# PLT_Demo_V2_R01.net
KiCad netlist of a schematic drawn in EAGLE
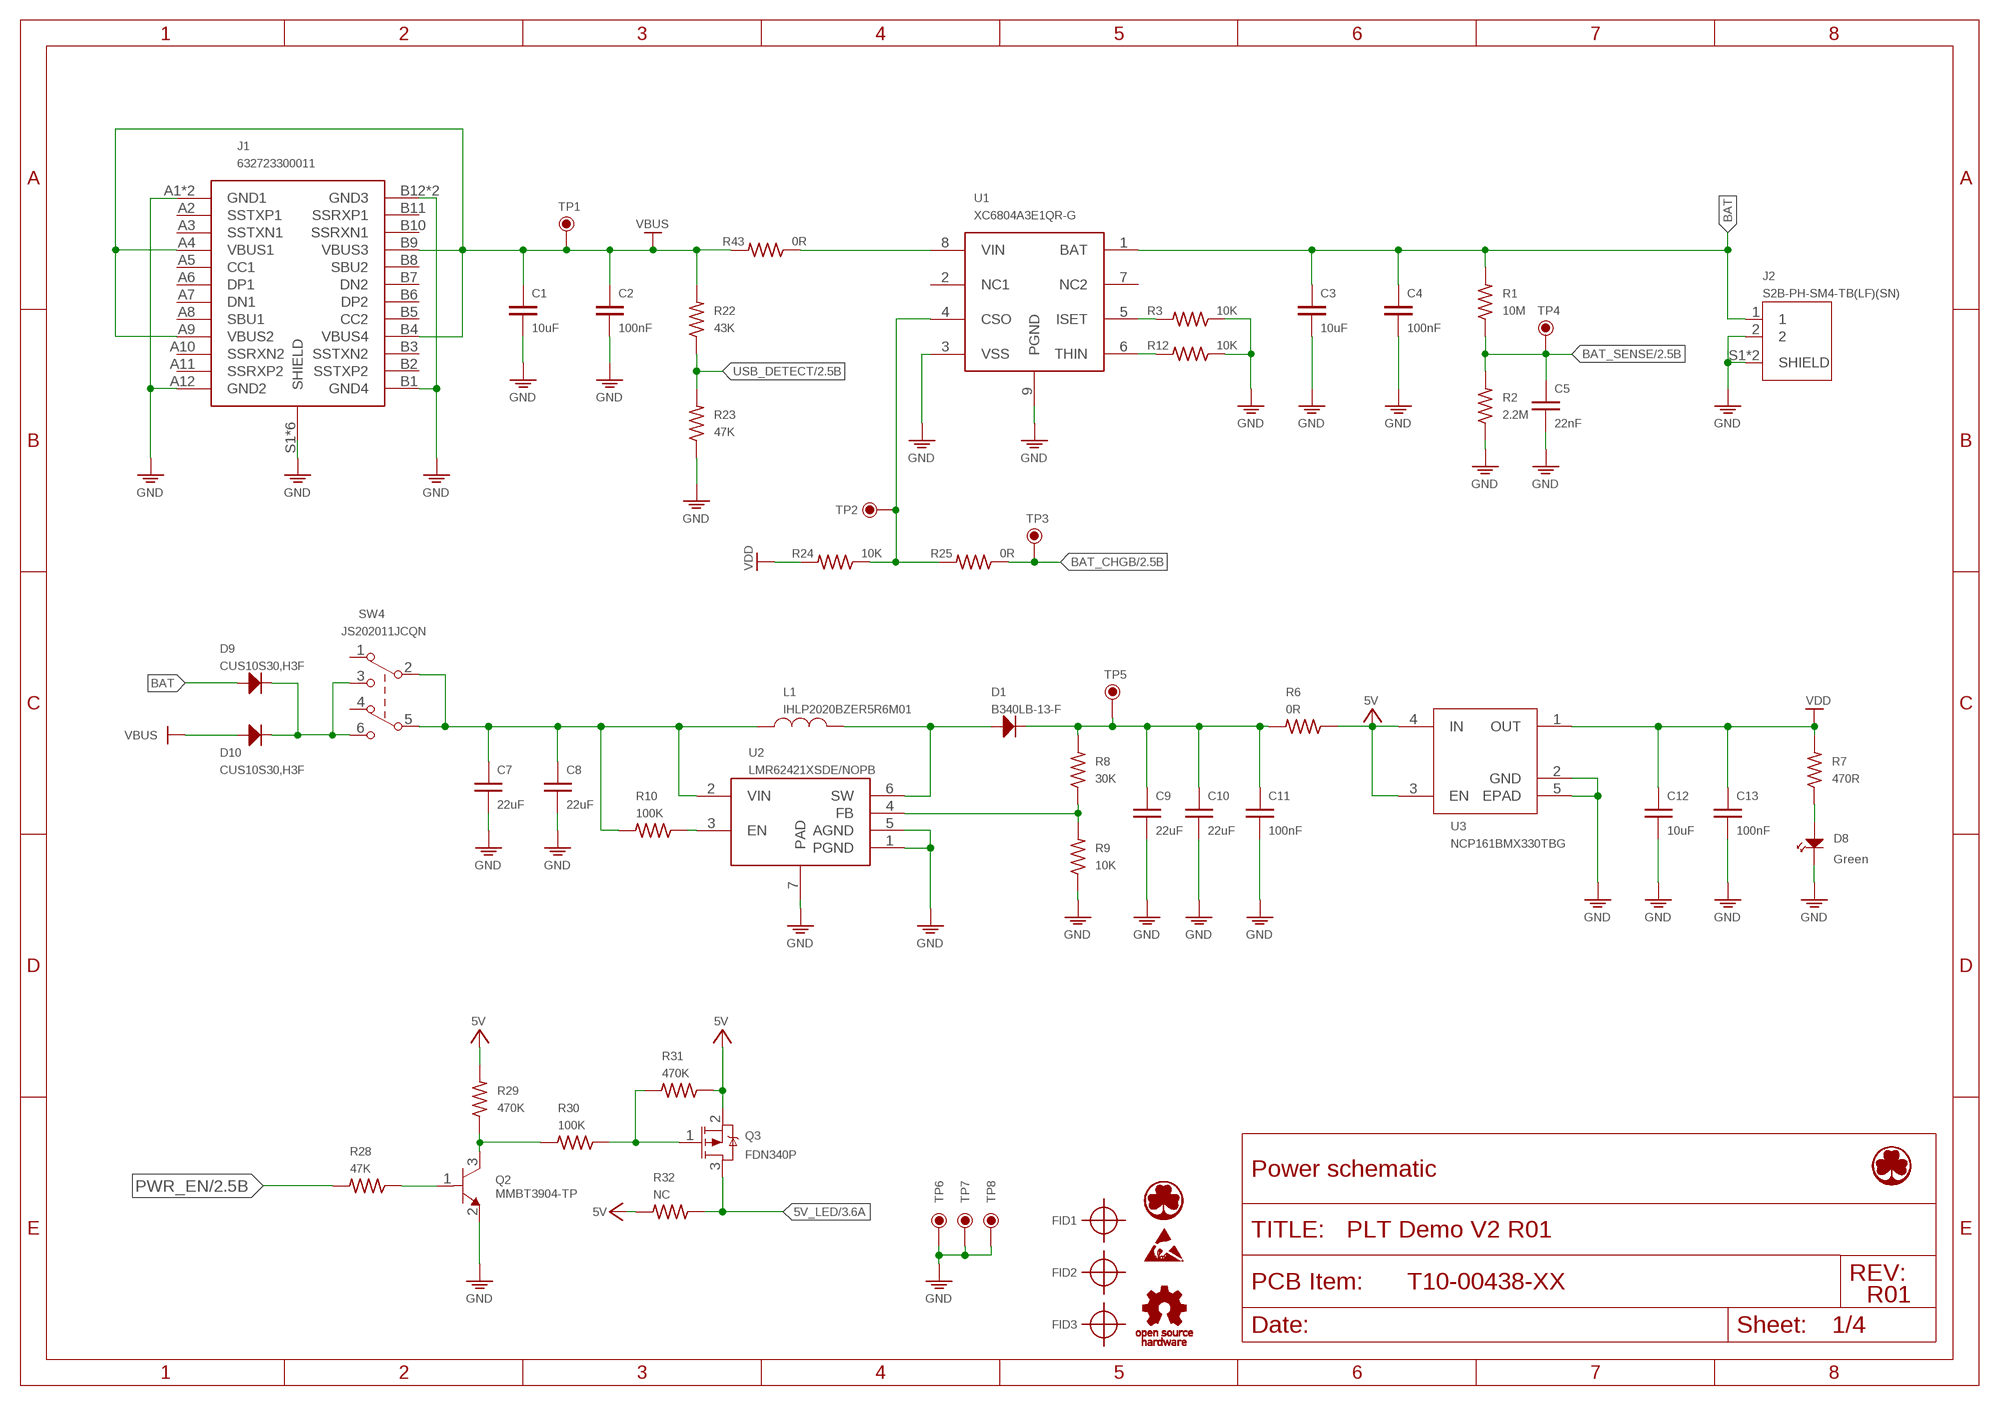
[diagram p0: schematic, sheet 1]
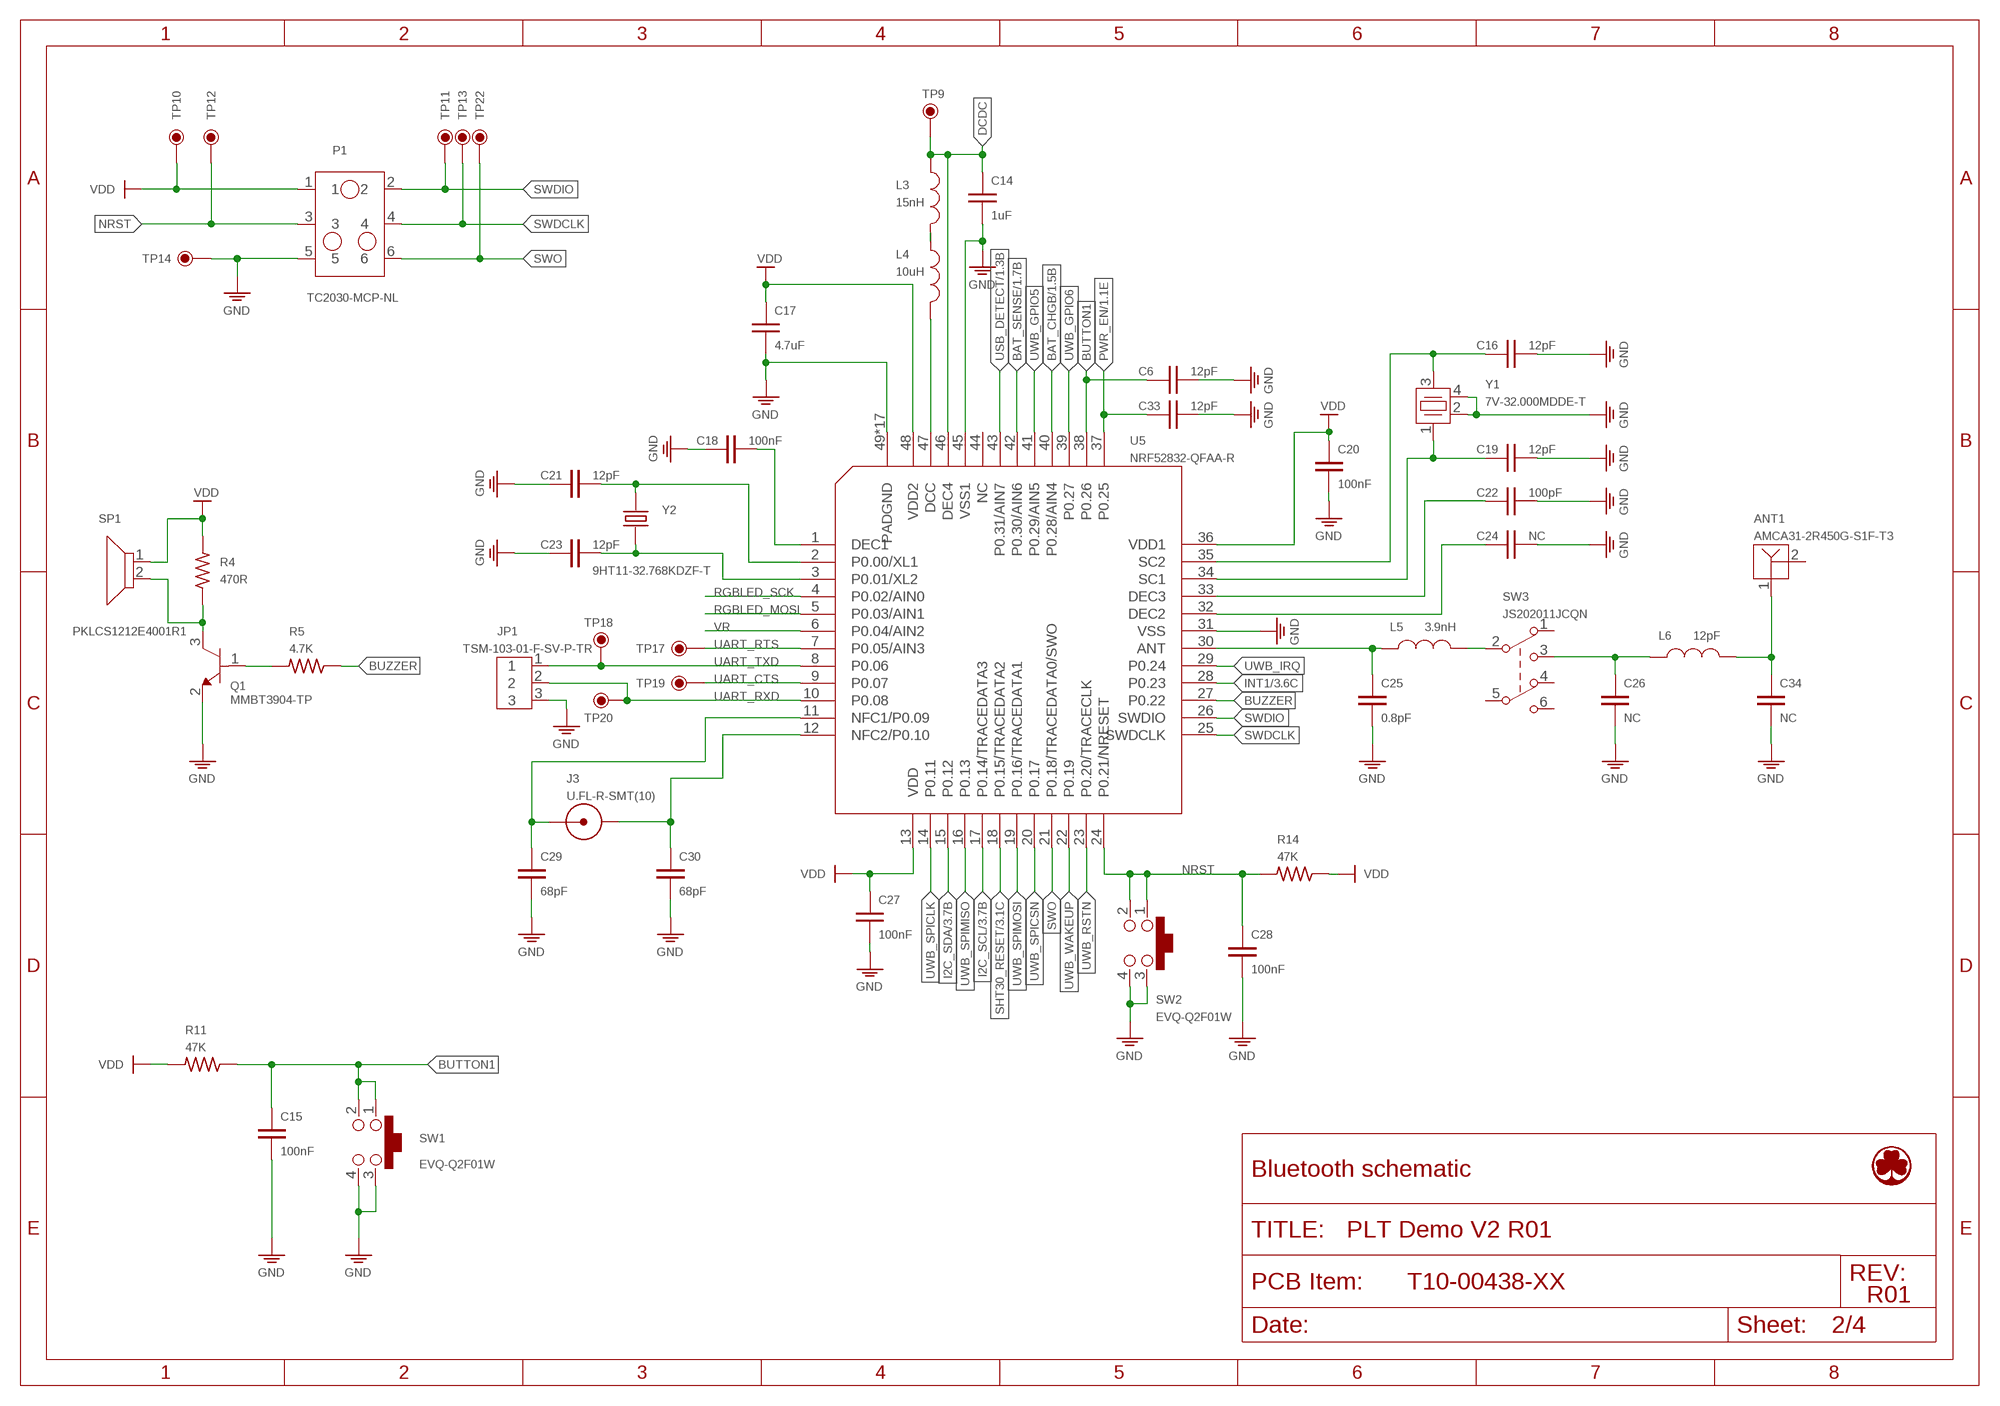
[diagram p1: schematic, sheet 2]
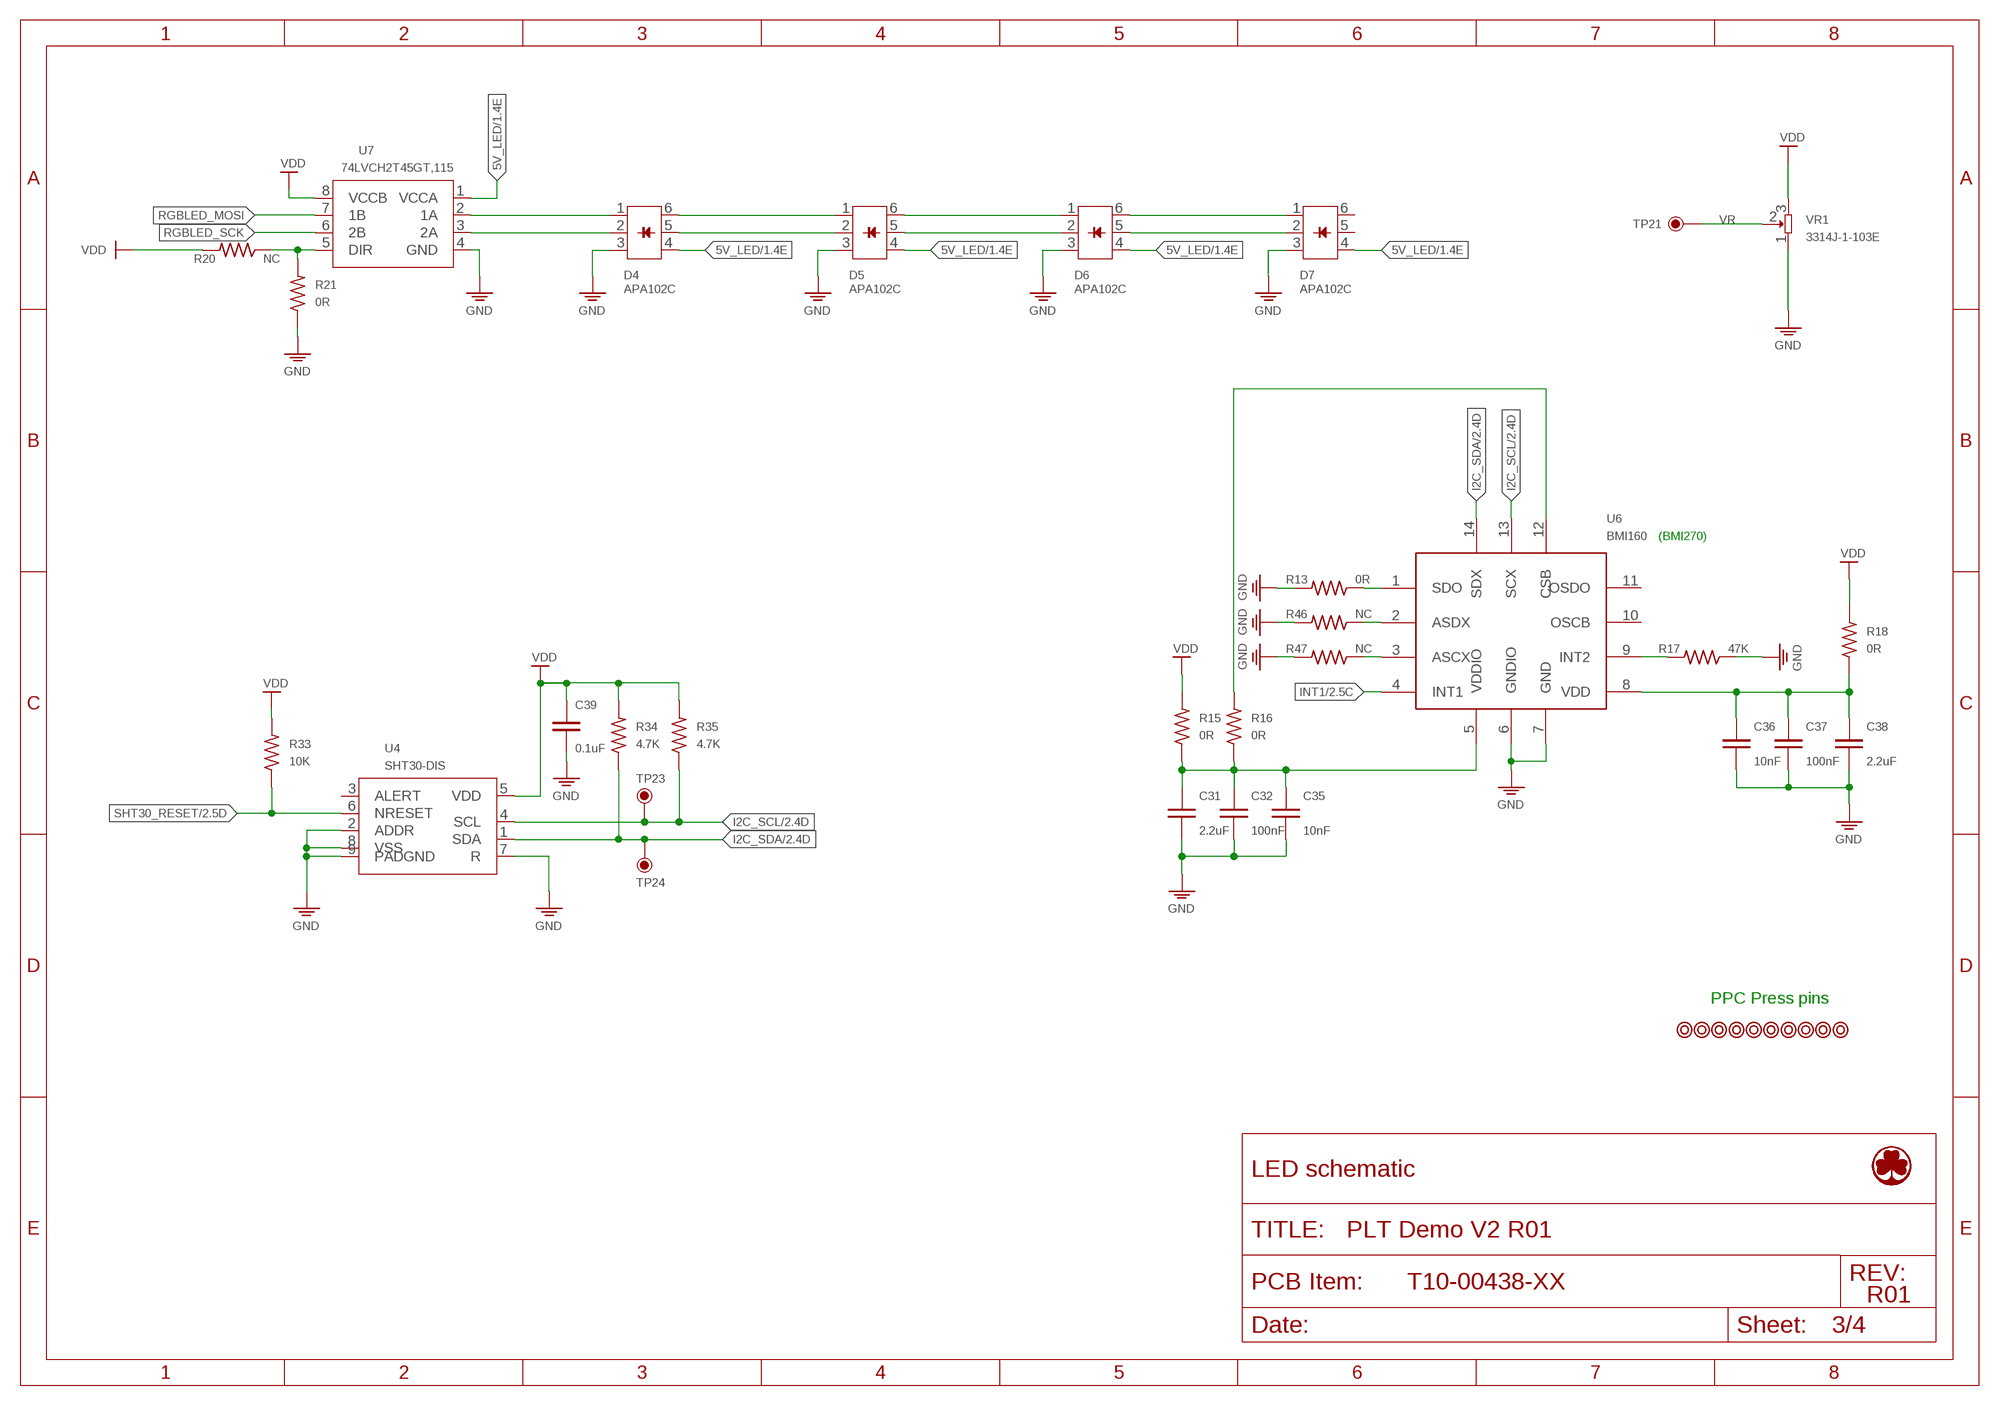
[diagram p2: schematic, sheet 3]
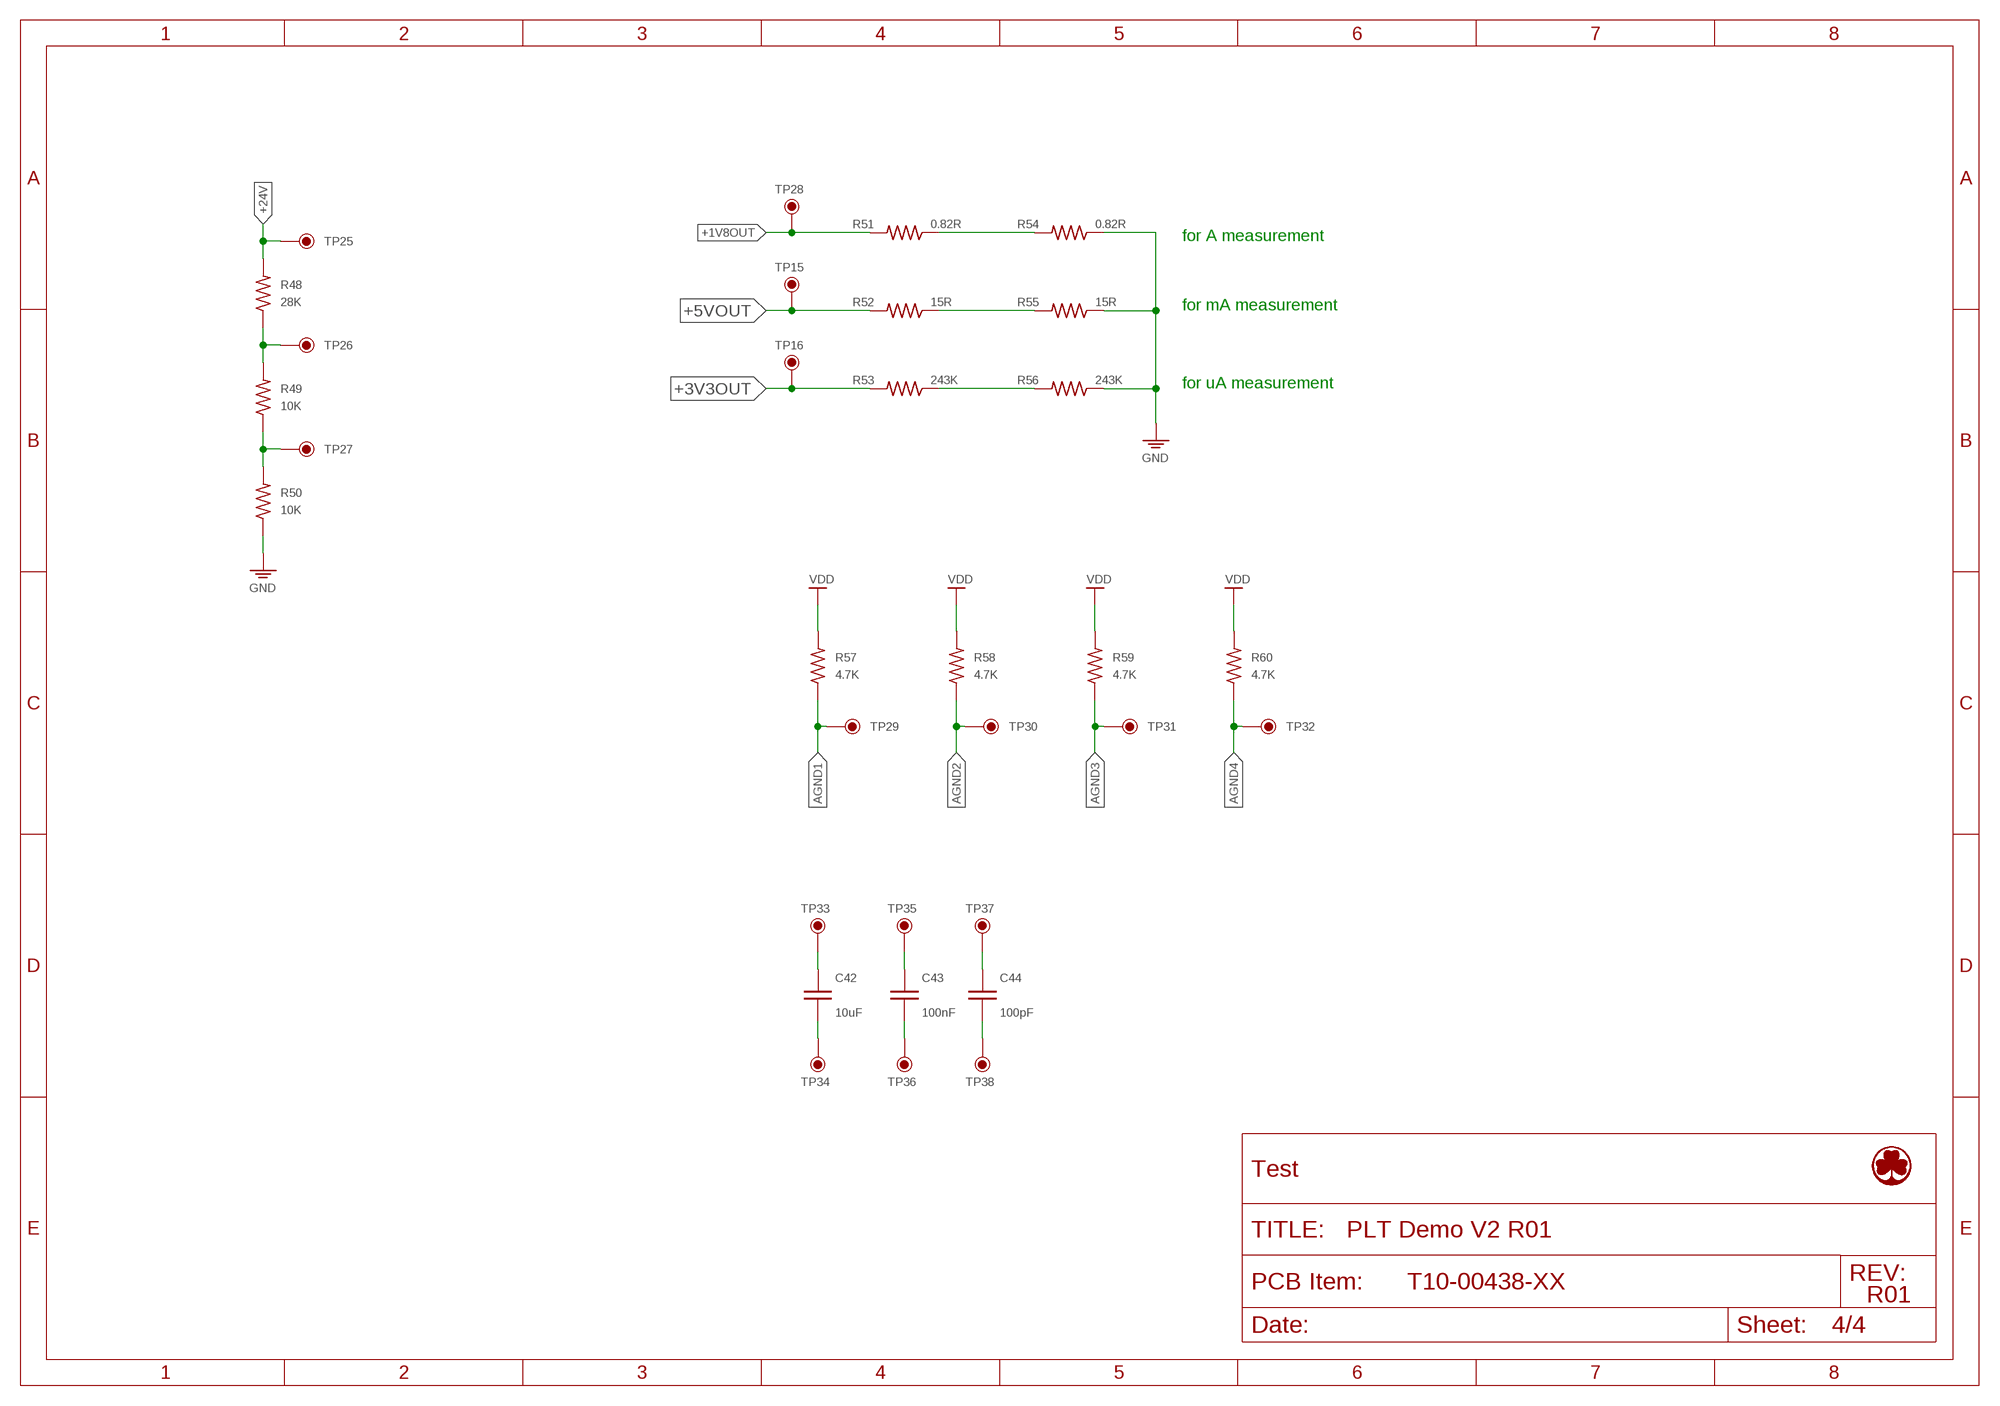
[diagram p3: schematic, sheet 4]

(export (version "E")
  (design (tool "Eeschema 10.0.6"))
  (components
    (comp (ref "ANT1")
      (value "AMCA31-2R450G-S1F-T3")
      (footprint "eagle-import:ANT_3216")
      (libsource (lib "eagle-import") (part "AMCA31-2R450G-S1F-T3"))
    )
    (comp (ref "C6")
      (value "12pF")
      (footprint "eagle-import:C0603")
      (libsource (lib "eagle-import") (part "CAPC0603"))
    )
    (comp (ref "C14")
      (value "1uF")
      (footprint "eagle-import:C0603")
      (libsource (lib "eagle-import") (part "CAPC0603"))
    )
    (comp (ref "C15")
      (value "100nF")
      (footprint "eagle-import:C0603")
      (libsource (lib "eagle-import") (part "CAPC0603"))
    )
    (comp (ref "C16")
      (value "12pF")
      (footprint "eagle-import:C0603")
      (libsource (lib "eagle-import") (part "CAPC0603"))
    )
    (comp (ref "C17")
      (value "4.7uF")
      (footprint "eagle-import:C0603")
      (libsource (lib "eagle-import") (part "CAPC0603"))
    )
    (comp (ref "C18")
      (value "100nF")
      (footprint "eagle-import:C0603")
      (libsource (lib "eagle-import") (part "CAPC0603"))
    )
    (comp (ref "C19")
      (value "12pF")
      (footprint "eagle-import:C0603")
      (libsource (lib "eagle-import") (part "CAPC0603"))
    )
    (comp (ref "C20")
      (value "100nF")
      (footprint "eagle-import:C0603")
      (libsource (lib "eagle-import") (part "CAPC0603"))
    )
    (comp (ref "C21")
      (value "12pF")
      (footprint "eagle-import:C0603")
      (libsource (lib "eagle-import") (part "CAPC0603"))
    )
    (comp (ref "C22")
      (value "100pF")
      (footprint "eagle-import:C0603")
      (libsource (lib "eagle-import") (part "CAPC0603"))
    )
    (comp (ref "C23")
      (value "12pF")
      (footprint "eagle-import:C0603")
      (libsource (lib "eagle-import") (part "CAPC0603"))
    )
    (comp (ref "C24")
      (value "NC")
      (footprint "eagle-import:C0603")
      (libsource (lib "eagle-import") (part "CAPC0603"))
    )
    (comp (ref "C25")
      (value "0.8pF")
      (footprint "eagle-import:C0603")
      (libsource (lib "eagle-import") (part "CAPC0603"))
    )
    (comp (ref "C26")
      (value "NC")
      (footprint "eagle-import:C0603")
      (libsource (lib "eagle-import") (part "CAPC0603"))
    )
    (comp (ref "C27")
      (value "100nF")
      (footprint "eagle-import:C0603")
      (libsource (lib "eagle-import") (part "CAPC0603"))
    )
    (comp (ref "C28")
      (value "100nF")
      (footprint "eagle-import:C0603")
      (libsource (lib "eagle-import") (part "CAPC0603"))
    )
    (comp (ref "C29")
      (value "68pF")
      (footprint "eagle-import:C0603")
      (libsource (lib "eagle-import") (part "CAPC0603"))
    )
    (comp (ref "C30")
      (value "68pF")
      (footprint "eagle-import:C0603")
      (libsource (lib "eagle-import") (part "CAPC0603"))
    )
    (comp (ref "C33")
      (value "12pF")
      (footprint "eagle-import:C0603")
      (libsource (lib "eagle-import") (part "CAPC0603"))
    )
    (comp (ref "C34")
      (value "NC")
      (footprint "eagle-import:C0603")
      (libsource (lib "eagle-import") (part "CAPC0603"))
    )
    (comp (ref "J3")
      (value "U.FL-R-SMT(10)")
      (footprint "eagle-import:U.FL-R-SMT(10)")
      (libsource (lib "eagle-import") (part "U.FL-R-SMT(10)"))
    )
    (comp (ref "JP1")
      (value "TSM-103-01-F-SV-P-TR")
      (footprint "eagle-import:JMP254P1X3V-SMT")
      (libsource (lib "eagle-import") (part "TSM-103-01-F-SV-P-TR"))
    )
    (comp (ref "L3")
      (value "15nH")
      (footprint "eagle-import:IND-0603")
      (libsource (lib "eagle-import") (part "INDUCTOR-2N0603"))
    )
    (comp (ref "L4")
      (value "10uH")
      (footprint "eagle-import:IND-0603")
      (libsource (lib "eagle-import") (part "INDUCTOR-2N0603"))
    )
    (comp (ref "L5")
      (value "3.9nH")
      (footprint "eagle-import:IND-0603")
      (libsource (lib "eagle-import") (part "INDUCTOR-2N0603"))
    )
    (comp (ref "L6")
      (value "12pF")
      (footprint "eagle-import:IND-0603")
      (libsource (lib "eagle-import") (part "INDUCTOR-2N0603"))
    )
    (comp (ref "P1")
      (value "TC2030-MCP-NL")
      (footprint "eagle-import:TC2030-IDC")
      (fields (field (name "MANUFACTURER_PART_NUMBER") "TC2030-MCP-NL-10-ND"))
      (libsource (lib "eagle-import") (part "TC2030-MCP-NL"))
    )
    (comp (ref "Q1")
      (value "MMBT3904-TP")
      (footprint "eagle-import:SOT23")
      (libsource (lib "eagle-import") (part "MMBT3904-TP"))
    )
    (comp (ref "R4")
      (value "470R")
      (footprint "eagle-import:R0603")
      (libsource (lib "eagle-import") (part "RESISTOR_USR0603"))
    )
    (comp (ref "R5")
      (value "4.7K")
      (footprint "eagle-import:R0603")
      (libsource (lib "eagle-import") (part "RESISTOR_USR0603"))
    )
    (comp (ref "R11")
      (value "47K")
      (footprint "eagle-import:R0603")
      (libsource (lib "eagle-import") (part "RESISTOR_USR0603"))
    )
    (comp (ref "R14")
      (value "47K")
      (footprint "eagle-import:R0603")
      (libsource (lib "eagle-import") (part "RESISTOR_USR0603"))
    )
    (comp (ref "SP1")
      (value "PKLCS1212E4001R1")
      (footprint "eagle-import:SPEAKER12X12_SMT")
      (libsource (lib "eagle-import") (part "PKLCS1212E4001R1"))
    )
    (comp (ref "SW1")
      (value "EVQ-Q2F01W")
      (footprint "eagle-import:SWITCH6.5X6_SMD")
      (libsource (lib "eagle-import") (part "SWITCH-4N-SMT"))
    )
    (comp (ref "SW2")
      (value "EVQ-Q2F01W")
      (footprint "eagle-import:SWITCH6.5X6_SMD")
      (libsource (lib "eagle-import") (part "SWITCH-4N-SMT"))
    )
    (comp (ref "SW3")
      (value "JS202011JCQN")
      (footprint "eagle-import:JS202011JCQN")
      (libsource (lib "eagle-import") (part "JS202011JCQN"))
    )
    (comp (ref "TP9")
      (value "TPTP1.0X0.5_DIP")
      (footprint "eagle-import:TP1.0X0.5_DIP")
      (libsource (lib "eagle-import") (part "TPTP1.0X0.5_DIP"))
    )
    (comp (ref "TP10")
      (value "TPTP1.0X0.5_DIP")
      (footprint "eagle-import:TP1.0X0.5_DIP")
      (libsource (lib "eagle-import") (part "TPTP1.0X0.5_DIP"))
    )
    (comp (ref "TP11")
      (value "TPTP1.0X0.5_DIP")
      (footprint "eagle-import:TP1.0X0.5_DIP")
      (libsource (lib "eagle-import") (part "TPTP1.0X0.5_DIP"))
    )
    (comp (ref "TP12")
      (value "TPTP1.0X0.5_DIP")
      (footprint "eagle-import:TP1.0X0.5_DIP")
      (libsource (lib "eagle-import") (part "TPTP1.0X0.5_DIP"))
    )
    (comp (ref "TP13")
      (value "TPTP1.0X0.5_DIP")
      (footprint "eagle-import:TP1.0X0.5_DIP")
      (libsource (lib "eagle-import") (part "TPTP1.0X0.5_DIP"))
    )
    (comp (ref "TP14")
      (value "TPTP1.0X0.5_DIP")
      (footprint "eagle-import:TP1.0X0.5_DIP")
      (libsource (lib "eagle-import") (part "TPTP1.0X0.5_DIP"))
    )
    (comp (ref "TP17")
      (value "TPTP1.0X0.5_DIP")
      (footprint "eagle-import:TP1.0X0.5_DIP")
      (libsource (lib "eagle-import") (part "TPTP1.0X0.5_DIP"))
    )
    (comp (ref "TP18")
      (value "TPTP1.0X0.5_DIP")
      (footprint "eagle-import:TP1.0X0.5_DIP")
      (libsource (lib "eagle-import") (part "TPTP1.0X0.5_DIP"))
    )
    (comp (ref "TP19")
      (value "TPTP1.0X0.5_DIP")
      (footprint "eagle-import:TP1.0X0.5_DIP")
      (libsource (lib "eagle-import") (part "TPTP1.0X0.5_DIP"))
    )
    (comp (ref "TP20")
      (value "TPTP1.0X0.5_DIP")
      (footprint "eagle-import:TP1.0X0.5_DIP")
      (libsource (lib "eagle-import") (part "TPTP1.0X0.5_DIP"))
    )
    (comp (ref "TP22")
      (value "TPTP1.0X0.5_DIP")
      (footprint "eagle-import:TP1.0X0.5_DIP")
      (libsource (lib "eagle-import") (part "TPTP1.0X0.5_DIP"))
    )
    (comp (ref "U5")
      (value "NRF52832-QFAA-R")
      (footprint "eagle-import:QFN040P6X6-48NV")
      (libsource (lib "eagle-import") (part "NRF52832-QFAA-R-48NV"))
    )
    (comp (ref "Y1")
      (value "7V-32.000MDDE-T")
      (footprint "eagle-import:OSC3.2X2.5-4N")
      (libsource (lib "eagle-import") (part "7V-32.000MDDE-T"))
    )
    (comp (ref "Y2")
      (value "9HT11-32.768KDZF-T")
      (footprint "eagle-import:OSC2X1.2-2N")
      (libsource (lib "eagle-import") (part "9HT11-32.768KDZF-T"))
    )
    (comp (ref "C31")
      (value "2.2uF")
      (footprint "eagle-import:C0603")
      (libsource (lib "eagle-import") (part "CAPC0603"))
    )
    (comp (ref "C32")
      (value "100nF")
      (footprint "eagle-import:C0603")
      (libsource (lib "eagle-import") (part "CAPC0603"))
    )
    (comp (ref "C35")
      (value "10nF")
      (footprint "eagle-import:C0603")
      (libsource (lib "eagle-import") (part "CAPC0603"))
    )
    (comp (ref "C36")
      (value "10nF")
      (footprint "eagle-import:C0603")
      (libsource (lib "eagle-import") (part "CAPC0603"))
    )
    (comp (ref "C37")
      (value "100nF")
      (footprint "eagle-import:C0603")
      (libsource (lib "eagle-import") (part "CAPC0603"))
    )
    (comp (ref "C38")
      (value "2.2uF")
      (footprint "eagle-import:C0603")
      (libsource (lib "eagle-import") (part "CAPC0603"))
    )
    (comp (ref "C39")
      (value "0.1uF")
      (footprint "eagle-import:C0603")
      (libsource (lib "eagle-import") (part "CAPC0603"))
    )
    (comp (ref "D4")
      (value "APA102C")
      (footprint "eagle-import:LED5X5-6N")
      (libsource (lib "eagle-import") (part "APA102C"))
    )
    (comp (ref "D5")
      (value "APA102C")
      (footprint "eagle-import:LED5X5-6N")
      (libsource (lib "eagle-import") (part "APA102C"))
    )
    (comp (ref "D6")
      (value "APA102C")
      (footprint "eagle-import:LED5X5-6N")
      (libsource (lib "eagle-import") (part "APA102C"))
    )
    (comp (ref "D7")
      (value "APA102C")
      (footprint "eagle-import:LED5X5-6N")
      (libsource (lib "eagle-import") (part "APA102C"))
    )
    (comp (ref "PIN1")
      (value "PRESS-PINS")
      (footprint "eagle-import:PRESS-PINS")
      (libsource (lib "eagle-import") (part "PRESS-PINS"))
    )
    (comp (ref "PIN2")
      (value "PRESS-PINS")
      (footprint "eagle-import:PRESS-PINS")
      (libsource (lib "eagle-import") (part "PRESS-PINS"))
    )
    (comp (ref "PIN3")
      (value "PRESS-PINS")
      (footprint "eagle-import:PRESS-PINS")
      (libsource (lib "eagle-import") (part "PRESS-PINS"))
    )
    (comp (ref "PIN4")
      (value "PRESS-PINS")
      (footprint "eagle-import:PRESS-PINS")
      (libsource (lib "eagle-import") (part "PRESS-PINS"))
    )
    (comp (ref "PIN5")
      (value "PRESS-PINS")
      (footprint "eagle-import:PRESS-PINS")
      (libsource (lib "eagle-import") (part "PRESS-PINS"))
    )
    (comp (ref "PIN6")
      (value "PRESS-PINS")
      (footprint "eagle-import:PRESS-PINS")
      (libsource (lib "eagle-import") (part "PRESS-PINS"))
    )
    (comp (ref "PIN7")
      (value "PRESS-PINS")
      (footprint "eagle-import:PRESS-PINS")
      (libsource (lib "eagle-import") (part "PRESS-PINS"))
    )
    (comp (ref "PIN8")
      (value "PRESS-PINS")
      (footprint "eagle-import:PRESS-PINS")
      (libsource (lib "eagle-import") (part "PRESS-PINS"))
    )
    (comp (ref "PIN9")
      (value "PRESS-PINS")
      (footprint "eagle-import:PRESS-PINS")
      (libsource (lib "eagle-import") (part "PRESS-PINS"))
    )
    (comp (ref "PIN10")
      (value "PRESS-PINS")
      (footprint "eagle-import:PRESS-PINS")
      (libsource (lib "eagle-import") (part "PRESS-PINS"))
    )
    (comp (ref "R13")
      (value "0R")
      (footprint "eagle-import:R0603")
      (libsource (lib "eagle-import") (part "RESISTOR_USR0603"))
    )
    (comp (ref "R15")
      (value "0R")
      (footprint "eagle-import:R0603")
      (libsource (lib "eagle-import") (part "RESISTOR_USR0603"))
    )
    (comp (ref "R16")
      (value "0R")
      (footprint "eagle-import:R0603")
      (libsource (lib "eagle-import") (part "RESISTOR_USR0603"))
    )
    (comp (ref "R17")
      (value "47K")
      (footprint "eagle-import:R0603")
      (libsource (lib "eagle-import") (part "RESISTOR_USR0603"))
    )
    (comp (ref "R18")
      (value "0R")
      (footprint "eagle-import:R0603")
      (libsource (lib "eagle-import") (part "RESISTOR_USR0603"))
    )
    (comp (ref "R20")
      (value "NC")
      (footprint "eagle-import:R0603")
      (libsource (lib "eagle-import") (part "RESISTOR_USR0603"))
    )
    (comp (ref "R21")
      (value "0R")
      (footprint "eagle-import:R0603")
      (libsource (lib "eagle-import") (part "RESISTOR_USR0603"))
    )
    (comp (ref "R33")
      (value "10K")
      (footprint "eagle-import:R0603")
      (libsource (lib "eagle-import") (part "RESISTOR_USR0603"))
    )
    (comp (ref "R34")
      (value "4.7K")
      (footprint "eagle-import:R0603")
      (libsource (lib "eagle-import") (part "RESISTOR_USR0603"))
    )
    (comp (ref "R35")
      (value "4.7K")
      (footprint "eagle-import:R0603")
      (libsource (lib "eagle-import") (part "RESISTOR_USR0603"))
    )
    (comp (ref "R46")
      (value "NC")
      (footprint "eagle-import:R0603")
      (libsource (lib "eagle-import") (part "RESISTOR_USR0603"))
    )
    (comp (ref "R47")
      (value "NC")
      (footprint "eagle-import:R0603")
      (libsource (lib "eagle-import") (part "RESISTOR_USR0603"))
    )
    (comp (ref "TP21")
      (value "TPTP1.0X0.5_DIP")
      (footprint "eagle-import:TP1.0X0.5_DIP")
      (libsource (lib "eagle-import") (part "TPTP1.0X0.5_DIP"))
    )
    (comp (ref "TP23")
      (value "TPTP1.0X0.5_DIP")
      (footprint "eagle-import:TP1.0X0.5_DIP")
      (libsource (lib "eagle-import") (part "TPTP1.0X0.5_DIP"))
    )
    (comp (ref "TP24")
      (value "TPTP1.0X0.5_DIP")
      (footprint "eagle-import:TP1.0X0.5_DIP")
      (libsource (lib "eagle-import") (part "TPTP1.0X0.5_DIP"))
    )
    (comp (ref "U4")
      (value "SHT30-DIS")
      (footprint "eagle-import:DFN050P2.5X2.5-8N")
      (libsource (lib "eagle-import") (part "SHT30-DISDFN050P2.5X2.5-8N"))
    )
    (comp (ref "U6")
      (value "BMI160")
      (footprint "eagle-import:LGA050P3X2.5-14N")
      (libsource (lib "eagle-import") (part "BMI160"))
    )
    (comp (ref "U7")
      (value "74LVCH2T45GT,115")
      (footprint "eagle-import:XSON8-SOT833-1")
      (libsource (lib "eagle-import") (part "74LVCH2T45GT,115"))
    )
    (comp (ref "VR1")
      (value "3314J-1-103E")
      (footprint "eagle-import:3314J-1-103E")
      (libsource (lib "eagle-import") (part "3314J-1-103E"))
    )
    (comp (ref "C42")
      (value "10uF")
      (footprint "eagle-import:C0805")
      (libsource (lib "eagle-import") (part "CAPC0805"))
    )
    (comp (ref "C43")
      (value "100nF")
      (footprint "eagle-import:C0603")
      (libsource (lib "eagle-import") (part "CAPC0603"))
    )
    (comp (ref "C44")
      (value "100pF")
      (footprint "eagle-import:C0603")
      (libsource (lib "eagle-import") (part "CAPC0603"))
    )
    (comp (ref "R48")
      (value "28K")
      (footprint "eagle-import:R0603")
      (libsource (lib "eagle-import") (part "RESISTOR_USR0603"))
    )
    (comp (ref "R49")
      (value "10K")
      (footprint "eagle-import:R0603")
      (libsource (lib "eagle-import") (part "RESISTOR_USR0603"))
    )
    (comp (ref "R50")
      (value "10K")
      (footprint "eagle-import:R0603")
      (libsource (lib "eagle-import") (part "RESISTOR_USR0603"))
    )
    (comp (ref "R51")
      (value "0.82R")
      (footprint "eagle-import:R1210")
      (libsource (lib "eagle-import") (part "RESISTOR_USR1210"))
    )
    (comp (ref "R52")
      (value "15R")
      (footprint "eagle-import:R0805")
      (libsource (lib "eagle-import") (part "RESISTOR_USR0805"))
    )
    (comp (ref "R53")
      (value "243K")
      (footprint "eagle-import:R0603")
      (libsource (lib "eagle-import") (part "RESISTOR_USR0603"))
    )
    (comp (ref "R54")
      (value "0.82R")
      (footprint "eagle-import:R1210")
      (libsource (lib "eagle-import") (part "RESISTOR_USR1210"))
    )
    (comp (ref "R55")
      (value "15R")
      (footprint "eagle-import:R0805")
      (libsource (lib "eagle-import") (part "RESISTOR_USR0805"))
    )
    (comp (ref "R56")
      (value "243K")
      (footprint "eagle-import:R0603")
      (libsource (lib "eagle-import") (part "RESISTOR_USR0603"))
    )
    (comp (ref "R57")
      (value "4.7K")
      (footprint "eagle-import:R0603")
      (libsource (lib "eagle-import") (part "RESISTOR_USR0603"))
    )
    (comp (ref "R58")
      (value "4.7K")
      (footprint "eagle-import:R0603")
      (libsource (lib "eagle-import") (part "RESISTOR_USR0603"))
    )
    (comp (ref "R59")
      (value "4.7K")
      (footprint "eagle-import:R0603")
      (libsource (lib "eagle-import") (part "RESISTOR_USR0603"))
    )
    (comp (ref "R60")
      (value "4.7K")
      (footprint "eagle-import:R0603")
      (libsource (lib "eagle-import") (part "RESISTOR_USR0603"))
    )
    (comp (ref "TP15")
      (value "TPTP1.0X0.5_DIP")
      (footprint "eagle-import:TP1.0X0.5_DIP")
      (libsource (lib "eagle-import") (part "TPTP1.0X0.5_DIP"))
    )
    (comp (ref "TP16")
      (value "TPTP1.0X0.5_DIP")
      (footprint "eagle-import:TP1.0X0.5_DIP")
      (libsource (lib "eagle-import") (part "TPTP1.0X0.5_DIP"))
    )
    (comp (ref "TP25")
      (value "TPTP1.0X0.5_DIP")
      (footprint "eagle-import:TP1.0X0.5_DIP")
      (libsource (lib "eagle-import") (part "TPTP1.0X0.5_DIP"))
    )
    (comp (ref "TP26")
      (value "TPTP1.0X0.5_DIP")
      (footprint "eagle-import:TP1.0X0.5_DIP")
      (libsource (lib "eagle-import") (part "TPTP1.0X0.5_DIP"))
    )
    (comp (ref "TP27")
      (value "TPTP1.0X0.5_DIP")
      (footprint "eagle-import:TP1.0X0.5_DIP")
      (libsource (lib "eagle-import") (part "TPTP1.0X0.5_DIP"))
    )
    (comp (ref "TP28")
      (value "TPTP1.0X0.5_DIP")
      (footprint "eagle-import:TP1.0X0.5_DIP")
      (libsource (lib "eagle-import") (part "TPTP1.0X0.5_DIP"))
    )
    (comp (ref "TP29")
      (value "TPTP1.0X0.5_DIP")
      (footprint "eagle-import:TP1.0X0.5_DIP")
      (libsource (lib "eagle-import") (part "TPTP1.0X0.5_DIP"))
    )
    (comp (ref "TP30")
      (value "TPTP1.0X0.5_DIP")
      (footprint "eagle-import:TP1.0X0.5_DIP")
      (libsource (lib "eagle-import") (part "TPTP1.0X0.5_DIP"))
    )
    (comp (ref "TP31")
      (value "TPTP1.0X0.5_DIP")
      (footprint "eagle-import:TP1.0X0.5_DIP")
      (libsource (lib "eagle-import") (part "TPTP1.0X0.5_DIP"))
    )
    (comp (ref "TP32")
      (value "TPTP1.0X0.5_DIP")
      (footprint "eagle-import:TP1.0X0.5_DIP")
      (libsource (lib "eagle-import") (part "TPTP1.0X0.5_DIP"))
    )
    (comp (ref "TP33")
      (value "TPTP1.0X0.5_DIP")
      (footprint "eagle-import:TP1.0X0.5_DIP")
      (libsource (lib "eagle-import") (part "TPTP1.0X0.5_DIP"))
    )
    (comp (ref "TP34")
      (value "TPTP1.0X0.5_DIP")
      (footprint "eagle-import:TP1.0X0.5_DIP")
      (libsource (lib "eagle-import") (part "TPTP1.0X0.5_DIP"))
    )
    (comp (ref "TP35")
      (value "TPTP1.0X0.5_DIP")
      (footprint "eagle-import:TP1.0X0.5_DIP")
      (libsource (lib "eagle-import") (part "TPTP1.0X0.5_DIP"))
    )
    (comp (ref "TP36")
      (value "TPTP1.0X0.5_DIP")
      (footprint "eagle-import:TP1.0X0.5_DIP")
      (libsource (lib "eagle-import") (part "TPTP1.0X0.5_DIP"))
    )
    (comp (ref "TP37")
      (value "TPTP1.0X0.5_DIP")
      (footprint "eagle-import:TP1.0X0.5_DIP")
      (libsource (lib "eagle-import") (part "TPTP1.0X0.5_DIP"))
    )
    (comp (ref "TP38")
      (value "TPTP1.0X0.5_DIP")
      (footprint "eagle-import:TP1.0X0.5_DIP")
      (libsource (lib "eagle-import") (part "TPTP1.0X0.5_DIP"))
    )
    (comp (ref "C1")
      (value "10uF")
      (footprint "eagle-import:C0603")
      (libsource (lib "eagle-import") (part "CAPC0603"))
    )
    (comp (ref "C2")
      (value "100nF")
      (footprint "eagle-import:C0603")
      (libsource (lib "eagle-import") (part "CAPC0603"))
    )
    (comp (ref "C3")
      (value "10uF")
      (footprint "eagle-import:C0603")
      (libsource (lib "eagle-import") (part "CAPC0603"))
    )
    (comp (ref "C4")
      (value "100nF")
      (footprint "eagle-import:C0603")
      (libsource (lib "eagle-import") (part "CAPC0603"))
    )
    (comp (ref "C5")
      (value "22nF")
      (footprint "eagle-import:C0603")
      (libsource (lib "eagle-import") (part "CAPC0603"))
    )
    (comp (ref "C7")
      (value "22uF")
      (footprint "eagle-import:C0603")
      (libsource (lib "eagle-import") (part "CAPC0603"))
    )
    (comp (ref "C8")
      (value "22uF")
      (footprint "eagle-import:C0603")
      (libsource (lib "eagle-import") (part "CAPC0603"))
    )
    (comp (ref "C9")
      (value "22uF")
      (footprint "eagle-import:C0603")
      (libsource (lib "eagle-import") (part "CAPC0603"))
    )
    (comp (ref "C10")
      (value "22uF")
      (footprint "eagle-import:C0603")
      (libsource (lib "eagle-import") (part "CAPC0603"))
    )
    (comp (ref "C11")
      (value "100nF")
      (footprint "eagle-import:C0603")
      (libsource (lib "eagle-import") (part "CAPC0603"))
    )
    (comp (ref "C12")
      (value "10uF")
      (footprint "eagle-import:C0603")
      (libsource (lib "eagle-import") (part "CAPC0603"))
    )
    (comp (ref "C13")
      (value "100nF")
      (footprint "eagle-import:C0603")
      (libsource (lib "eagle-import") (part "CAPC0603"))
    )
    (comp (ref "D1")
      (value "B340LB-13-F")
      (footprint "eagle-import:SMB")
      (libsource (lib "eagle-import") (part "B340LB-13-F"))
    )
    (comp (ref "D8")
      (value "Green")
      (footprint "eagle-import:LED0603")
      (libsource (lib "eagle-import") (part "LED-SMTLED0603"))
    )
    (comp (ref "D9")
      (value "CUS10S30,H3F")
      (footprint "eagle-import:SOD-323")
      (libsource (lib "eagle-import") (part "CUS10S30,H3F"))
    )
    (comp (ref "D10")
      (value "CUS10S30,H3F")
      (footprint "eagle-import:SOD-323")
      (libsource (lib "eagle-import") (part "CUS10S30,H3F"))
    )
    (comp (ref "FID1")
      (value "SENSOR_MISC_FIDUCIAL-1MM")
      (footprint "eagle-import:SENSOR_MISC_FIDUCIAL-1MM")
      (libsource (lib "eagle-import") (part "SENSOR_MISC_FIDUCIAL-1MM"))
    )
    (comp (ref "FID2")
      (value "SENSOR_MISC_FIDUCIAL-1MM")
      (footprint "eagle-import:SENSOR_MISC_FIDUCIAL-1MM")
      (libsource (lib "eagle-import") (part "SENSOR_MISC_FIDUCIAL-1MM"))
    )
    (comp (ref "FID3")
      (value "SENSOR_MISC_FIDUCIAL-1MM")
      (footprint "eagle-import:SENSOR_MISC_FIDUCIAL-1MM")
      (libsource (lib "eagle-import") (part "SENSOR_MISC_FIDUCIAL-1MM"))
    )
    (comp (ref "J1")
      (value "632723300011")
      (footprint "eagle-import:632723X00011")
      (libsource (lib "eagle-import") (part "632723X00011"))
    )
    (comp (ref "J2")
      (value "S2B-PH-SM4-TB(LF)(SN)")
      (footprint "eagle-import:S2B-PH-SM4-TB(LF)(SN)")
      (libsource (lib "eagle-import") (part "S2B-PH-SM4-TB(LF)(SN)"))
    )
    (comp (ref "L1")
      (value "IHLP2020BZER5R6M01")
      (footprint "eagle-import:IND-5220_SMD")
      (libsource (lib "eagle-import") (part "IHLP2020BZER5R6M01"))
    )
    (comp (ref "Q2")
      (value "MMBT3904-TP")
      (footprint "eagle-import:SOT23")
      (libsource (lib "eagle-import") (part "MMBT3904-TP"))
    )
    (comp (ref "Q3")
      (value "FDN340P")
      (footprint "eagle-import:SOT23")
      (libsource (lib "eagle-import") (part "FDN340P"))
    )
    (comp (ref "R1")
      (value "10M")
      (footprint "eagle-import:R0603")
      (libsource (lib "eagle-import") (part "RESISTOR_USR0603"))
    )
    (comp (ref "R2")
      (value "2.2M")
      (footprint "eagle-import:R0603")
      (libsource (lib "eagle-import") (part "RESISTOR_USR0603"))
    )
    (comp (ref "R3")
      (value "10K")
      (footprint "eagle-import:R0603")
      (libsource (lib "eagle-import") (part "RESISTOR_USR0603"))
    )
    (comp (ref "R6")
      (value "0R")
      (footprint "eagle-import:R0603")
      (libsource (lib "eagle-import") (part "RESISTOR_USR0603"))
    )
    (comp (ref "R7")
      (value "470R")
      (footprint "eagle-import:R0603")
      (libsource (lib "eagle-import") (part "RESISTOR_USR0603"))
    )
    (comp (ref "R8")
      (value "30K")
      (footprint "eagle-import:R0603")
      (libsource (lib "eagle-import") (part "RESISTOR_USR0603"))
    )
    (comp (ref "R9")
      (value "10K")
      (footprint "eagle-import:R0603")
      (libsource (lib "eagle-import") (part "RESISTOR_USR0603"))
    )
    (comp (ref "R10")
      (value "100K")
      (footprint "eagle-import:R0603")
      (libsource (lib "eagle-import") (part "RESISTOR_USR0603"))
    )
    (comp (ref "R12")
      (value "10K")
      (footprint "eagle-import:R0603")
      (libsource (lib "eagle-import") (part "RESISTOR_USR0603"))
    )
    (comp (ref "R22")
      (value "43K")
      (footprint "eagle-import:R0603")
      (libsource (lib "eagle-import") (part "RESISTOR_USR0603"))
    )
    (comp (ref "R23")
      (value "47K")
      (footprint "eagle-import:R0603")
      (libsource (lib "eagle-import") (part "RESISTOR_USR0603"))
    )
    (comp (ref "R24")
      (value "10K")
      (footprint "eagle-import:R0603")
      (libsource (lib "eagle-import") (part "RESISTOR_USR0603"))
    )
    (comp (ref "R25")
      (value "0R")
      (footprint "eagle-import:R0603")
      (libsource (lib "eagle-import") (part "RESISTOR_USR0603"))
    )
    (comp (ref "R28")
      (value "47K")
      (footprint "eagle-import:R0603")
      (libsource (lib "eagle-import") (part "RESISTOR_USR0603"))
    )
    (comp (ref "R29")
      (value "470K")
      (footprint "eagle-import:R0603")
      (libsource (lib "eagle-import") (part "RESISTOR_USR0603"))
    )
    (comp (ref "R30")
      (value "100K")
      (footprint "eagle-import:R0603")
      (libsource (lib "eagle-import") (part "RESISTOR_USR0603"))
    )
    (comp (ref "R31")
      (value "470K")
      (footprint "eagle-import:R0603")
      (libsource (lib "eagle-import") (part "RESISTOR_USR0603"))
    )
    (comp (ref "R32")
      (value "NC")
      (footprint "eagle-import:R0603")
      (libsource (lib "eagle-import") (part "RESISTOR_USR0603"))
    )
    (comp (ref "R43")
      (value "0R")
      (footprint "eagle-import:R0603")
      (libsource (lib "eagle-import") (part "RESISTOR_USR0603"))
    )
    (comp (ref "SW4")
      (value "JS202011JCQN")
      (footprint "eagle-import:JS202011JCQN")
      (libsource (lib "eagle-import") (part "JS202011JCQN"))
    )
    (comp (ref "TP1")
      (value "TPTP1.0X0.5_DIP")
      (footprint "eagle-import:TP1.0X0.5_DIP")
      (libsource (lib "eagle-import") (part "TPTP1.0X0.5_DIP"))
    )
    (comp (ref "TP2")
      (value "TPTP1.0X0.5_DIP")
      (footprint "eagle-import:TP1.0X0.5_DIP")
      (libsource (lib "eagle-import") (part "TPTP1.0X0.5_DIP"))
    )
    (comp (ref "TP3")
      (value "TPTP1.0X0.5_DIP")
      (footprint "eagle-import:TP1.0X0.5_DIP")
      (libsource (lib "eagle-import") (part "TPTP1.0X0.5_DIP"))
    )
    (comp (ref "TP4")
      (value "TPTP1.0X0.5_DIP")
      (footprint "eagle-import:TP1.0X0.5_DIP")
      (libsource (lib "eagle-import") (part "TPTP1.0X0.5_DIP"))
    )
    (comp (ref "TP5")
      (value "TPTP1.0X0.5_DIP")
      (footprint "eagle-import:TP1.0X0.5_DIP")
      (libsource (lib "eagle-import") (part "TPTP1.0X0.5_DIP"))
    )
    (comp (ref "TP6")
      (value "TPTP1.0X0.5_DIP")
      (footprint "eagle-import:TP1.0X0.5_DIP")
      (libsource (lib "eagle-import") (part "TPTP1.0X0.5_DIP"))
    )
    (comp (ref "TP7")
      (value "TPTP1.0X0.5_DIP")
      (footprint "eagle-import:TP1.0X0.5_DIP")
      (libsource (lib "eagle-import") (part "TPTP1.0X0.5_DIP"))
    )
    (comp (ref "TP8")
      (value "TPTP1.0X0.5_DIP")
      (footprint "eagle-import:TP1.0X0.5_DIP")
      (libsource (lib "eagle-import") (part "TPTP1.0X0.5_DIP"))
    )
    (comp (ref "U$4")
      (value "BCD-LOGO")
      (footprint "eagle-import:BCD-LOGO")
      (libsource (lib "eagle-import") (part "BCD-LOGO"))
    )
    (comp (ref "U$5")
      (value "ANTI-STATIC")
      (footprint "eagle-import:ANTI-STATIC")
      (libsource (lib "eagle-import") (part "ANTI-STATIC"))
    )
    (comp (ref "U$6")
      (value "OSHW-LOGO-R2000")
      (footprint "eagle-import:OSHW-LOGO-R2000")
      (libsource (lib "eagle-import") (part "OSHW-LOGO-R2000"))
    )
    (comp (ref "U1")
      (value "XC6804A3E1QR-G")
      (footprint "eagle-import:SOP127P6X1.6-8NP")
      (libsource (lib "eagle-import") (part "XC6804A3E1QR-G"))
    )
    (comp (ref "U2")
      (value "LMR62421XSDE/NOPB")
      (footprint "eagle-import:WSON095P3X3-6NPAD")
      (libsource (lib "eagle-import") (part "LMR62421XSDE/NOPB"))
    )
    (comp (ref "U3")
      (value "NCP161BMX330TBG")
      (footprint "eagle-import:XDFN4")
      (libsource (lib "eagle-import") (part "NCP161BMX330TBG"))
    )
  )
  (nets
    (net (code "1") (name "+1V8OUT") (class "Default")
      (node (ref "R51") (pin "2") (pinfunction "2_2") (pintype "passive"))
      (node (ref "TP28") (pin "1") (pinfunction "1_1") (pintype "bidirectional"))
    )
    (net (code "2") (name "+3V3OUT") (class "Default")
      (node (ref "R53") (pin "2") (pinfunction "2_2") (pintype "passive"))
      (node (ref "TP16") (pin "1") (pinfunction "1_1") (pintype "bidirectional"))
    )
    (net (code "3") (name "+5VOUT") (class "Default")
      (node (ref "R52") (pin "2") (pinfunction "2_2") (pintype "passive"))
      (node (ref "TP15") (pin "1") (pinfunction "1_1") (pintype "bidirectional"))
    )
    (net (code "4") (name "+24V") (class "Default")
      (node (ref "R48") (pin "2") (pinfunction "2_2") (pintype "passive"))
      (node (ref "TP25") (pin "1") (pinfunction "1_1") (pintype "bidirectional"))
    )
    (net (code "5") (name "5V") (class "Default")
      (node (ref "Q3") (pin "2") (pinfunction "S_2") (pintype "bidirectional"))
      (node (ref "R29") (pin "2") (pinfunction "2_2") (pintype "passive"))
      (node (ref "R31") (pin "1") (pinfunction "1_1") (pintype "passive"))
      (node (ref "R32") (pin "2") (pinfunction "2_2") (pintype "passive"))
      (node (ref "R6") (pin "1") (pinfunction "1_1") (pintype "passive"))
      (node (ref "U3") (pin "3") (pinfunction "EN_3") (pintype "bidirectional"))
      (node (ref "U3") (pin "4") (pinfunction "IN_4") (pintype "bidirectional"))
    )
    (net (code "6") (name "5V_LED") (class "Default")
      (node (ref "D4") (pin "4") (pinfunction "4_4") (pintype "bidirectional"))
      (node (ref "D5") (pin "4") (pinfunction "4_4") (pintype "bidirectional"))
      (node (ref "D6") (pin "4") (pinfunction "4_4") (pintype "bidirectional"))
      (node (ref "D7") (pin "4") (pinfunction "4_4") (pintype "bidirectional"))
      (node (ref "Q3") (pin "3") (pinfunction "D_3") (pintype "bidirectional"))
      (node (ref "R32") (pin "1") (pinfunction "1_1") (pintype "passive"))
      (node (ref "U7") (pin "1") (pinfunction "VCCA_1") (pintype "bidirectional"))
    )
    (net (code "7") (name "AGND1") (class "Default")
      (node (ref "R57") (pin "1") (pinfunction "1_1") (pintype "passive"))
      (node (ref "TP29") (pin "1") (pinfunction "1_1") (pintype "bidirectional"))
    )
    (net (code "8") (name "AGND2") (class "Default")
      (node (ref "R58") (pin "1") (pinfunction "1_1") (pintype "passive"))
      (node (ref "TP30") (pin "1") (pinfunction "1_1") (pintype "bidirectional"))
    )
    (net (code "9") (name "AGND3") (class "Default")
      (node (ref "R59") (pin "1") (pinfunction "1_1") (pintype "passive"))
      (node (ref "TP31") (pin "1") (pinfunction "1_1") (pintype "bidirectional"))
    )
    (net (code "10") (name "AGND4") (class "Default")
      (node (ref "R60") (pin "1") (pinfunction "1_1") (pintype "passive"))
      (node (ref "TP32") (pin "1") (pinfunction "1_1") (pintype "bidirectional"))
    )
    (net (code "11") (name "BAT") (class "Default")
      (node (ref "C3") (pin "1") (pinfunction "1_1") (pintype "bidirectional"))
      (node (ref "C4") (pin "1") (pinfunction "1_1") (pintype "bidirectional"))
      (node (ref "D9") (pin "1") (pinfunction "1_1") (pintype "bidirectional"))
      (node (ref "J2") (pin "1") (pinfunction "1_1") (pintype "bidirectional"))
      (node (ref "R1") (pin "2") (pinfunction "2_2") (pintype "passive"))
      (node (ref "U1") (pin "1") (pinfunction "BAT_1") (pintype "bidirectional"))
    )
    (net (code "12") (name "BAT_CHGB") (class "Default")
      (node (ref "R25") (pin "1") (pinfunction "1_1") (pintype "passive"))
      (node (ref "TP3") (pin "1") (pinfunction "1_1") (pintype "bidirectional"))
      (node (ref "U5") (pin "40") (pinfunction "P0.28/AIN4_40") (pintype "bidirectional"))
    )
    (net (code "13") (name "BAT_SENSE") (class "Default")
      (node (ref "C5") (pin "1") (pinfunction "1_1") (pintype "bidirectional"))
      (node (ref "R1") (pin "1") (pinfunction "1_1") (pintype "passive"))
      (node (ref "R2") (pin "2") (pinfunction "2_2") (pintype "passive"))
      (node (ref "TP4") (pin "1") (pinfunction "1_1") (pintype "bidirectional"))
      (node (ref "U5") (pin "42") (pinfunction "P0.30/AIN6_42") (pintype "bidirectional"))
    )
    (net (code "14") (name "BUTTON1") (class "Default")
      (node (ref "C15") (pin "1") (pinfunction "1_1") (pintype "bidirectional"))
      (node (ref "C6") (pin "1") (pinfunction "1_1") (pintype "bidirectional"))
      (node (ref "R11") (pin "1") (pinfunction "1_1") (pintype "passive"))
      (node (ref "SW1") (pin "1") (pinfunction "1_1") (pintype "bidirectional"))
      (node (ref "SW1") (pin "2") (pinfunction "2_2") (pintype "bidirectional"))
      (node (ref "U5") (pin "38") (pinfunction "P0.26_38") (pintype "bidirectional"))
    )
    (net (code "15") (name "BUZZER") (class "Default")
      (node (ref "R5") (pin "1") (pinfunction "1_1") (pintype "passive"))
      (node (ref "U5") (pin "27") (pinfunction "P0.22_27") (pintype "bidirectional"))
    )
    (net (code "16") (name "DCDC") (class "Default")
      (node (ref "C14") (pin "1") (pinfunction "1_1") (pintype "bidirectional"))
      (node (ref "L3") (pin "1") (pinfunction "1_1") (pintype "bidirectional"))
      (node (ref "TP9") (pin "1") (pinfunction "1_1") (pintype "bidirectional"))
      (node (ref "U5") (pin "46") (pinfunction "DEC4_46") (pintype "bidirectional"))
    )
    (net (code "17") (name "GND") (class "Default")
      (node (ref "C1") (pin "2") (pinfunction "2_2") (pintype "bidirectional"))
      (node (ref "C10") (pin "2") (pinfunction "2_2") (pintype "bidirectional"))
      (node (ref "C11") (pin "2") (pinfunction "2_2") (pintype "bidirectional"))
      (node (ref "C12") (pin "2") (pinfunction "2_2") (pintype "bidirectional"))
      (node (ref "C13") (pin "2") (pinfunction "2_2") (pintype "bidirectional"))
      (node (ref "C14") (pin "2") (pinfunction "2_2") (pintype "bidirectional"))
      (node (ref "C15") (pin "2") (pinfunction "2_2") (pintype "bidirectional"))
      (node (ref "C16") (pin "2") (pinfunction "2_2") (pintype "bidirectional"))
      (node (ref "C17") (pin "2") (pinfunction "2_2") (pintype "bidirectional"))
      (node (ref "C18") (pin "1") (pinfunction "1_1") (pintype "bidirectional"))
      (node (ref "C19") (pin "2") (pinfunction "2_2") (pintype "bidirectional"))
      (node (ref "C2") (pin "2") (pinfunction "2_2") (pintype "bidirectional"))
      (node (ref "C20") (pin "2") (pinfunction "2_2") (pintype "bidirectional"))
      (node (ref "C21") (pin "1") (pinfunction "1_1") (pintype "bidirectional"))
      (node (ref "C22") (pin "2") (pinfunction "2_2") (pintype "bidirectional"))
      (node (ref "C23") (pin "1") (pinfunction "1_1") (pintype "bidirectional"))
      (node (ref "C24") (pin "2") (pinfunction "2_2") (pintype "bidirectional"))
      (node (ref "C25") (pin "2") (pinfunction "2_2") (pintype "bidirectional"))
      (node (ref "C26") (pin "2") (pinfunction "2_2") (pintype "bidirectional"))
      (node (ref "C27") (pin "2") (pinfunction "2_2") (pintype "bidirectional"))
      (node (ref "C28") (pin "2") (pinfunction "2_2") (pintype "bidirectional"))
      (node (ref "C29") (pin "2") (pinfunction "2_2") (pintype "bidirectional"))
      (node (ref "C3") (pin "2") (pinfunction "2_2") (pintype "bidirectional"))
      (node (ref "C30") (pin "2") (pinfunction "2_2") (pintype "bidirectional"))
      (node (ref "C31") (pin "2") (pinfunction "2_2") (pintype "bidirectional"))
      (node (ref "C32") (pin "2") (pinfunction "2_2") (pintype "bidirectional"))
      (node (ref "C33") (pin "2") (pinfunction "2_2") (pintype "bidirectional"))
      (node (ref "C34") (pin "2") (pinfunction "2_2") (pintype "bidirectional"))
      (node (ref "C35") (pin "2") (pinfunction "2_2") (pintype "bidirectional"))
      (node (ref "C36") (pin "2") (pinfunction "2_2") (pintype "bidirectional"))
      (node (ref "C37") (pin "2") (pinfunction "2_2") (pintype "bidirectional"))
      (node (ref "C38") (pin "2") (pinfunction "2_2") (pintype "bidirectional"))
      (node (ref "C39") (pin "1") (pinfunction "1_1") (pintype "bidirectional"))
      (node (ref "C4") (pin "2") (pinfunction "2_2") (pintype "bidirectional"))
      (node (ref "C5") (pin "2") (pinfunction "2_2") (pintype "bidirectional"))
      (node (ref "C6") (pin "2") (pinfunction "2_2") (pintype "bidirectional"))
      (node (ref "C7") (pin "2") (pinfunction "2_2") (pintype "bidirectional"))
      (node (ref "C8") (pin "2") (pinfunction "2_2") (pintype "bidirectional"))
      (node (ref "C9") (pin "2") (pinfunction "2_2") (pintype "bidirectional"))
      (node (ref "D4") (pin "3") (pinfunction "3_3") (pintype "bidirectional"))
      (node (ref "D5") (pin "3") (pinfunction "3_3") (pintype "bidirectional"))
      (node (ref "D6") (pin "3") (pinfunction "3_3") (pintype "bidirectional"))
      (node (ref "D7") (pin "3") (pinfunction "3_3") (pintype "bidirectional"))
      (node (ref "D8") (pin "2") (pinfunction "2_2") (pintype "bidirectional"))
      (node (ref "J1") (pin "A1") (pinfunction "GND1_A1") (pintype "power_in"))
      (node (ref "J1") (pin "A12") (pinfunction "GND2_A12") (pintype "power_in"))
      (node (ref "J1") (pin "B1") (pinfunction "GND4_B1") (pintype "power_in"))
      (node (ref "J1") (pin "B12") (pinfunction "GND3_B12") (pintype "power_in"))
      (node (ref "J1") (pin "GND") (pinfunction "GND1_GND") (pintype "power_in"))
      (node (ref "J1") (pin "GND1") (pinfunction "GND3_GND1") (pintype "power_in"))
      (node (ref "J1") (pin "S1") (pinfunction "SHIELD_S1") (pintype "power_in"))
      (node (ref "J1") (pin "S2") (pinfunction "SHIELD_S2") (pintype "power_in"))
      (node (ref "J1") (pin "S3") (pinfunction "SHIELD_S3") (pintype "power_in"))
      (node (ref "J1") (pin "S4") (pinfunction "SHIELD_S4") (pintype "power_in"))
      (node (ref "J1") (pin "S5") (pinfunction "SHIELD_S5") (pintype "power_in"))
      (node (ref "J1") (pin "S6") (pinfunction "SHIELD_S6") (pintype "power_in"))
      (node (ref "J2") (pin "2") (pinfunction "2_2") (pintype "bidirectional"))
      (node (ref "J2") (pin "S1") (pinfunction "SHIELD_S1") (pintype "bidirectional"))
      (node (ref "J2") (pin "S2") (pinfunction "SHIELD_S2") (pintype "bidirectional"))
      (node (ref "JP1") (pin "3") (pinfunction "3_3") (pintype "bidirectional"))
      (node (ref "P1") (pin "5") (pinfunction "5_5") (pintype "bidirectional"))
      (node (ref "Q1") (pin "2") (pinfunction "E_2") (pintype "bidirectional"))
      (node (ref "Q2") (pin "2") (pinfunction "E_2") (pintype "bidirectional"))
      (node (ref "R12") (pin "1") (pinfunction "1_1") (pintype "passive"))
      (node (ref "R13") (pin "2") (pinfunction "2_2") (pintype "passive"))
      (node (ref "R17") (pin "1") (pinfunction "1_1") (pintype "passive"))
      (node (ref "R2") (pin "1") (pinfunction "1_1") (pintype "passive"))
      (node (ref "R21") (pin "1") (pinfunction "1_1") (pintype "passive"))
      (node (ref "R23") (pin "1") (pinfunction "1_1") (pintype "passive"))
      (node (ref "R3") (pin "1") (pinfunction "1_1") (pintype "passive"))
      (node (ref "R46") (pin "2") (pinfunction "2_2") (pintype "passive"))
      (node (ref "R47") (pin "2") (pinfunction "2_2") (pintype "passive"))
      (node (ref "R50") (pin "1") (pinfunction "1_1") (pintype "passive"))
      (node (ref "R54") (pin "1") (pinfunction "1_1") (pintype "passive"))
      (node (ref "R55") (pin "1") (pinfunction "1_1") (pintype "passive"))
      (node (ref "R56") (pin "1") (pinfunction "1_1") (pintype "passive"))
      (node (ref "R9") (pin "1") (pinfunction "1_1") (pintype "passive"))
      (node (ref "SW1") (pin "3") (pinfunction "3_3") (pintype "bidirectional"))
      (node (ref "SW1") (pin "4") (pinfunction "4_4") (pintype "bidirectional"))
      (node (ref "SW2") (pin "3") (pinfunction "3_3") (pintype "bidirectional"))
      (node (ref "SW2") (pin "4") (pinfunction "4_4") (pintype "bidirectional"))
      (node (ref "TP14") (pin "1") (pinfunction "1_1") (pintype "bidirectional"))
      (node (ref "TP6") (pin "1") (pinfunction "1_1") (pintype "bidirectional"))
      (node (ref "TP7") (pin "1") (pinfunction "1_1") (pintype "bidirectional"))
      (node (ref "TP8") (pin "1") (pinfunction "1_1") (pintype "bidirectional"))
      (node (ref "U1") (pin "3") (pinfunction "VSS_3") (pintype "bidirectional"))
      (node (ref "U1") (pin "9") (pinfunction "PGND_9") (pintype "bidirectional"))
      (node (ref "U2") (pin "1") (pinfunction "PGND_1") (pintype "bidirectional"))
      (node (ref "U2") (pin "5") (pinfunction "AGND_5") (pintype "bidirectional"))
      (node (ref "U2") (pin "7") (pinfunction "PAD_7") (pintype "bidirectional"))
      (node (ref "U3") (pin "2") (pinfunction "GND_2") (pintype "bidirectional"))
      (node (ref "U3") (pin "5") (pinfunction "EPAD_5") (pintype "bidirectional"))
      (node (ref "U4") (pin "2") (pinfunction "ADDR_2") (pintype "bidirectional"))
      (node (ref "U4") (pin "7") (pinfunction "R_7") (pintype "bidirectional"))
      (node (ref "U4") (pin "8") (pinfunction "VSS_8") (pintype "bidirectional"))
      (node (ref "U4") (pin "9") (pinfunction "PADGND_9") (pintype "bidirectional"))
      (node (ref "U5") (pin "31") (pinfunction "VSS_31") (pintype "bidirectional"))
      (node (ref "U5") (pin "45") (pinfunction "VSS1_45") (pintype "bidirectional"))
      (node (ref "U5") (pin "49") (pinfunction "PADGND_49") (pintype "bidirectional"))
      (node (ref "U5") (pin "P$1") (pinfunction "PADGND_P$1") (pintype "bidirectional"))
      (node (ref "U5") (pin "P$10") (pinfunction "PADGND_P$10") (pintype "bidirectional"))
      (node (ref "U5") (pin "P$11") (pinfunction "PADGND_P$11") (pintype "bidirectional"))
      (node (ref "U5") (pin "P$12") (pinfunction "PADGND_P$12") (pintype "bidirectional"))
      (node (ref "U5") (pin "P$13") (pinfunction "PADGND_P$13") (pintype "bidirectional"))
      (node (ref "U5") (pin "P$14") (pinfunction "PADGND_P$14") (pintype "bidirectional"))
      (node (ref "U5") (pin "P$15") (pinfunction "PADGND_P$15") (pintype "bidirectional"))
      (node (ref "U5") (pin "P$16") (pinfunction "PADGND_P$16") (pintype "bidirectional"))
      (node (ref "U5") (pin "P$2") (pinfunction "PADGND_P$2") (pintype "bidirectional"))
      (node (ref "U5") (pin "P$3") (pinfunction "PADGND_P$3") (pintype "bidirectional"))
      (node (ref "U5") (pin "P$4") (pinfunction "PADGND_P$4") (pintype "bidirectional"))
      (node (ref "U5") (pin "P$5") (pinfunction "PADGND_P$5") (pintype "bidirectional"))
      (node (ref "U5") (pin "P$6") (pinfunction "PADGND_P$6") (pintype "bidirectional"))
      (node (ref "U5") (pin "P$7") (pinfunction "PADGND_P$7") (pintype "bidirectional"))
      (node (ref "U5") (pin "P$8") (pinfunction "PADGND_P$8") (pintype "bidirectional"))
      (node (ref "U5") (pin "P$9") (pinfunction "PADGND_P$9") (pintype "bidirectional"))
      (node (ref "U6") (pin "6") (pinfunction "GNDIO_6") (pintype "bidirectional"))
      (node (ref "U6") (pin "7") (pinfunction "GND_7") (pintype "bidirectional"))
      (node (ref "U7") (pin "4") (pinfunction "GND_4") (pintype "bidirectional"))
      (node (ref "VR1") (pin "1") (pinfunction "1_1") (pintype "bidirectional"))
      (node (ref "Y1") (pin "2") (pinfunction "2_2") (pintype "bidirectional"))
      (node (ref "Y1") (pin "4") (pinfunction "4_4") (pintype "bidirectional"))
    )
    (net (code "18") (name "I2C_SCL") (class "Default")
      (node (ref "R35") (pin "1") (pinfunction "1_1") (pintype "passive"))
      (node (ref "TP23") (pin "1") (pinfunction "1_1") (pintype "bidirectional"))
      (node (ref "U4") (pin "4") (pinfunction "SCL_4") (pintype "bidirectional"))
      (node (ref "U5") (pin "17") (pinfunction "P0.14/TRACEDATA3_17") (pintype "bidirectional"))
      (node (ref "U6") (pin "13") (pinfunction "SCX_13") (pintype "bidirectional"))
    )
    (net (code "19") (name "I2C_SDA") (class "Default")
      (node (ref "R34") (pin "1") (pinfunction "1_1") (pintype "passive"))
      (node (ref "TP24") (pin "1") (pinfunction "1_1") (pintype "bidirectional"))
      (node (ref "U4") (pin "1") (pinfunction "SDA_1") (pintype "bidirectional"))
      (node (ref "U5") (pin "15") (pinfunction "P0.12_15") (pintype "bidirectional"))
      (node (ref "U6") (pin "14") (pinfunction "SDX_14") (pintype "bidirectional"))
    )
    (net (code "20") (name "INT1") (class "Default")
      (node (ref "U5") (pin "28") (pinfunction "P0.23_28") (pintype "bidirectional"))
      (node (ref "U6") (pin "4") (pinfunction "INT1_4") (pintype "bidirectional"))
    )
    (net (code "21") (name "NRST") (class "Default")
      (node (ref "C28") (pin "1") (pinfunction "1_1") (pintype "bidirectional"))
      (node (ref "P1") (pin "3") (pinfunction "3_3") (pintype "bidirectional"))
      (node (ref "R14") (pin "2") (pinfunction "2_2") (pintype "passive"))
      (node (ref "SW2") (pin "1") (pinfunction "1_1") (pintype "bidirectional"))
      (node (ref "SW2") (pin "2") (pinfunction "2_2") (pintype "bidirectional"))
      (node (ref "TP12") (pin "1") (pinfunction "1_1") (pintype "bidirectional"))
      (node (ref "U5") (pin "24") (pinfunction "P0.21/NRESET_24") (pintype "bidirectional"))
    )
    (net (code "22") (name "Net-(ANT1-Pad1)") (class "Default")
      (node (ref "ANT1") (pin "1") (pinfunction "1_1") (pintype "bidirectional"))
      (node (ref "C34") (pin "1") (pinfunction "1_1") (pintype "bidirectional"))
      (node (ref "L6") (pin "2") (pinfunction "2_2") (pintype "bidirectional"))
    )
    (net (code "23") (name "Net-(C10-Pad1)") (class "Default")
      (node (ref "C10") (pin "1") (pinfunction "1_1") (pintype "bidirectional"))
      (node (ref "C11") (pin "1") (pinfunction "1_1") (pintype "bidirectional"))
      (node (ref "C9") (pin "1") (pinfunction "1_1") (pintype "bidirectional"))
      (node (ref "D1") (pin "2") (pinfunction "2_2") (pintype "bidirectional"))
      (node (ref "R6") (pin "2") (pinfunction "2_2") (pintype "passive"))
      (node (ref "R8") (pin "2") (pinfunction "2_2") (pintype "passive"))
      (node (ref "TP5") (pin "1") (pinfunction "1_1") (pintype "bidirectional"))
    )
    (net (code "24") (name "Net-(C26-Pad1)") (class "Default")
      (node (ref "C26") (pin "1") (pinfunction "1_1") (pintype "bidirectional"))
      (node (ref "L6") (pin "1") (pinfunction "1_1") (pintype "bidirectional"))
      (node (ref "SW3") (pin "3") (pinfunction "3_3") (pintype "bidirectional"))
    )
    (net (code "25") (name "Net-(C42-Pad1)") (class "Default")
      (node (ref "C42") (pin "1") (pinfunction "1_1") (pintype "bidirectional"))
      (node (ref "TP33") (pin "1") (pinfunction "1_1") (pintype "bidirectional"))
    )
    (net (code "26") (name "Net-(C42-Pad2)") (class "Default")
      (node (ref "C42") (pin "2") (pinfunction "2_2") (pintype "bidirectional"))
      (node (ref "TP34") (pin "1") (pinfunction "1_1") (pintype "bidirectional"))
    )
    (net (code "27") (name "Net-(C43-Pad1)") (class "Default")
      (node (ref "C43") (pin "1") (pinfunction "1_1") (pintype "bidirectional"))
      (node (ref "TP35") (pin "1") (pinfunction "1_1") (pintype "bidirectional"))
    )
    (net (code "28") (name "Net-(C43-Pad2)") (class "Default")
      (node (ref "C43") (pin "2") (pinfunction "2_2") (pintype "bidirectional"))
      (node (ref "TP36") (pin "1") (pinfunction "1_1") (pintype "bidirectional"))
    )
    (net (code "29") (name "Net-(C44-Pad1)") (class "Default")
      (node (ref "C44") (pin "1") (pinfunction "1_1") (pintype "bidirectional"))
      (node (ref "TP37") (pin "1") (pinfunction "1_1") (pintype "bidirectional"))
    )
    (net (code "30") (name "Net-(C44-Pad2)") (class "Default")
      (node (ref "C44") (pin "2") (pinfunction "2_2") (pintype "bidirectional"))
      (node (ref "TP38") (pin "1") (pinfunction "1_1") (pintype "bidirectional"))
    )
    (net (code "31") (name "Net-(D4-Pad5)") (class "Default")
      (node (ref "D4") (pin "5") (pinfunction "5_5") (pintype "bidirectional"))
      (node (ref "D5") (pin "2") (pinfunction "2_2") (pintype "bidirectional"))
    )
    (net (code "32") (name "Net-(D4-Pad6)") (class "Default")
      (node (ref "D4") (pin "6") (pinfunction "6_6") (pintype "bidirectional"))
      (node (ref "D5") (pin "1") (pinfunction "1_1") (pintype "bidirectional"))
    )
    (net (code "33") (name "Net-(D5-Pad5)") (class "Default")
      (node (ref "D5") (pin "5") (pinfunction "5_5") (pintype "bidirectional"))
      (node (ref "D6") (pin "2") (pinfunction "2_2") (pintype "bidirectional"))
    )
    (net (code "34") (name "Net-(D5-Pad6)") (class "Default")
      (node (ref "D5") (pin "6") (pinfunction "6_6") (pintype "bidirectional"))
      (node (ref "D6") (pin "1") (pinfunction "1_1") (pintype "bidirectional"))
    )
    (net (code "35") (name "Net-(D6-Pad5)") (class "Default")
      (node (ref "D6") (pin "5") (pinfunction "5_5") (pintype "bidirectional"))
      (node (ref "D7") (pin "2") (pinfunction "2_2") (pintype "bidirectional"))
    )
    (net (code "36") (name "Net-(D6-Pad6)") (class "Default")
      (node (ref "D6") (pin "6") (pinfunction "6_6") (pintype "bidirectional"))
      (node (ref "D7") (pin "1") (pinfunction "1_1") (pintype "bidirectional"))
    )
    (net (code "37") (name "Net-(D8-Pad1)") (class "Default")
      (node (ref "D8") (pin "1") (pinfunction "1_1") (pintype "bidirectional"))
      (node (ref "R7") (pin "1") (pinfunction "1_1") (pintype "passive"))
    )
    (net (code "38") (name "Net-(D10-Pad2)") (class "Default")
      (node (ref "D10") (pin "2") (pinfunction "2_2") (pintype "bidirectional"))
      (node (ref "D9") (pin "2") (pinfunction "2_2") (pintype "bidirectional"))
      (node (ref "SW4") (pin "3") (pinfunction "3_3") (pintype "bidirectional"))
      (node (ref "SW4") (pin "6") (pinfunction "6_6") (pintype "bidirectional"))
    )
    (net (code "39") (name "Net-(L3-Pad2)") (class "Default")
      (node (ref "L3") (pin "2") (pinfunction "2_2") (pintype "bidirectional"))
      (node (ref "L4") (pin "1") (pinfunction "1_1") (pintype "bidirectional"))
    )
    (net (code "40") (name "Net-(L5-Pad2)") (class "Default")
      (node (ref "L5") (pin "2") (pinfunction "2_2") (pintype "bidirectional"))
      (node (ref "SW3") (pin "2") (pinfunction "2_2") (pintype "bidirectional"))
    )
    (net (code "41") (name "Net-(Q1-B)") (class "Default")
      (node (ref "Q1") (pin "1") (pinfunction "B_1") (pintype "bidirectional"))
      (node (ref "R5") (pin "2") (pinfunction "2_2") (pintype "passive"))
    )
    (net (code "42") (name "Net-(Q1-C)") (class "Default")
      (node (ref "Q1") (pin "3") (pinfunction "C_3") (pintype "bidirectional"))
      (node (ref "R4") (pin "1") (pinfunction "1_1") (pintype "passive"))
      (node (ref "SP1") (pin "2") (pinfunction "2_2") (pintype "bidirectional"))
    )
    (net (code "43") (name "Net-(Q2-B)") (class "Default")
      (node (ref "Q2") (pin "1") (pinfunction "B_1") (pintype "bidirectional"))
      (node (ref "R28") (pin "1") (pinfunction "1_1") (pintype "passive"))
    )
    (net (code "44") (name "Net-(Q2-C)") (class "Default")
      (node (ref "Q2") (pin "3") (pinfunction "C_3") (pintype "bidirectional"))
      (node (ref "R29") (pin "1") (pinfunction "1_1") (pintype "passive"))
      (node (ref "R30") (pin "2") (pinfunction "2_2") (pintype "passive"))
    )
    (net (code "45") (name "Net-(Q3-G)") (class "Default")
      (node (ref "Q3") (pin "1") (pinfunction "G_1") (pintype "bidirectional"))
      (node (ref "R30") (pin "1") (pinfunction "1_1") (pintype "passive"))
      (node (ref "R31") (pin "2") (pinfunction "2_2") (pintype "passive"))
    )
    (net (code "46") (name "Net-(R48-Pad1)") (class "Default")
      (node (ref "R48") (pin "1") (pinfunction "1_1") (pintype "passive"))
      (node (ref "R49") (pin "2") (pinfunction "2_2") (pintype "passive"))
      (node (ref "TP26") (pin "1") (pinfunction "1_1") (pintype "bidirectional"))
    )
    (net (code "47") (name "Net-(R49-Pad1)") (class "Default")
      (node (ref "R49") (pin "1") (pinfunction "1_1") (pintype "passive"))
      (node (ref "R50") (pin "2") (pinfunction "2_2") (pintype "passive"))
      (node (ref "TP27") (pin "1") (pinfunction "1_1") (pintype "bidirectional"))
    )
    (net (code "48") (name "Net-(R51-Pad1)") (class "Default")
      (node (ref "R51") (pin "1") (pinfunction "1_1") (pintype "passive"))
      (node (ref "R54") (pin "2") (pinfunction "2_2") (pintype "passive"))
    )
    (net (code "49") (name "Net-(R52-Pad1)") (class "Default")
      (node (ref "R52") (pin "1") (pinfunction "1_1") (pintype "passive"))
      (node (ref "R55") (pin "2") (pinfunction "2_2") (pintype "passive"))
    )
    (net (code "50") (name "Net-(R53-Pad1)") (class "Default")
      (node (ref "R53") (pin "1") (pinfunction "1_1") (pintype "passive"))
      (node (ref "R56") (pin "2") (pinfunction "2_2") (pintype "passive"))
    )
    (net (code "51") (name "Net-(U1-CSO)") (class "Default")
      (node (ref "R24") (pin "1") (pinfunction "1_1") (pintype "passive"))
      (node (ref "R25") (pin "2") (pinfunction "2_2") (pintype "passive"))
      (node (ref "TP2") (pin "1") (pinfunction "1_1") (pintype "bidirectional"))
      (node (ref "U1") (pin "4") (pinfunction "CSO_4") (pintype "bidirectional"))
    )
    (net (code "52") (name "Net-(U1-ISET)") (class "Default")
      (node (ref "R3") (pin "2") (pinfunction "2_2") (pintype "passive"))
      (node (ref "U1") (pin "5") (pinfunction "ISET_5") (pintype "bidirectional"))
    )
    (net (code "53") (name "Net-(U1-THIN)") (class "Default")
      (node (ref "R12") (pin "2") (pinfunction "2_2") (pintype "passive"))
      (node (ref "U1") (pin "6") (pinfunction "THIN_6") (pintype "bidirectional"))
    )
    (net (code "54") (name "Net-(U1-VIN)") (class "Default")
      (node (ref "R43") (pin "1") (pinfunction "1_1") (pintype "passive"))
      (node (ref "U1") (pin "8") (pinfunction "VIN_8") (pintype "bidirectional"))
    )
    (net (code "55") (name "Net-(U2-EN)") (class "Default")
      (node (ref "R10") (pin "1") (pinfunction "1_1") (pintype "passive"))
      (node (ref "U2") (pin "3") (pinfunction "EN_3") (pintype "bidirectional"))
    )
    (net (code "56") (name "Net-(U2-FB)") (class "Default")
      (node (ref "R8") (pin "1") (pinfunction "1_1") (pintype "passive"))
      (node (ref "R9") (pin "2") (pinfunction "2_2") (pintype "passive"))
      (node (ref "U2") (pin "4") (pinfunction "FB_4") (pintype "bidirectional"))
    )
    (net (code "57") (name "Net-(U2-SW)") (class "Default")
      (node (ref "D1") (pin "1") (pinfunction "1_1") (pintype "bidirectional"))
      (node (ref "L1") (pin "2") (pinfunction "2_2") (pintype "bidirectional"))
      (node (ref "U2") (pin "6") (pinfunction "SW_6") (pintype "bidirectional"))
    )
    (net (code "58") (name "Net-(U2-VIN)") (class "Default")
      (node (ref "C7") (pin "1") (pinfunction "1_1") (pintype "bidirectional"))
      (node (ref "C8") (pin "1") (pinfunction "1_1") (pintype "bidirectional"))
      (node (ref "L1") (pin "1") (pinfunction "1_1") (pintype "bidirectional"))
      (node (ref "R10") (pin "2") (pinfunction "2_2") (pintype "passive"))
      (node (ref "SW4") (pin "2") (pinfunction "2_2") (pintype "bidirectional"))
      (node (ref "SW4") (pin "5") (pinfunction "5_5") (pintype "bidirectional"))
      (node (ref "U2") (pin "2") (pinfunction "VIN_2") (pintype "bidirectional"))
    )
    (net (code "59") (name "Net-(U5-ANT)") (class "Default")
      (node (ref "C25") (pin "1") (pinfunction "1_1") (pintype "bidirectional"))
      (node (ref "L5") (pin "1") (pinfunction "1_1") (pintype "bidirectional"))
      (node (ref "U5") (pin "30") (pinfunction "ANT_30") (pintype "bidirectional"))
    )
    (net (code "60") (name "Net-(U5-DCC)") (class "Default")
      (node (ref "L4") (pin "2") (pinfunction "2_2") (pintype "bidirectional"))
      (node (ref "U5") (pin "47") (pinfunction "DCC_47") (pintype "bidirectional"))
    )
    (net (code "61") (name "Net-(U5-DEC1)") (class "Default")
      (node (ref "C18") (pin "2") (pinfunction "2_2") (pintype "bidirectional"))
      (node (ref "U5") (pin "1") (pinfunction "DEC1_1") (pintype "bidirectional"))
    )
    (net (code "62") (name "Net-(U5-DEC2)") (class "Default")
      (node (ref "C24") (pin "1") (pinfunction "1_1") (pintype "bidirectional"))
      (node (ref "U5") (pin "32") (pinfunction "DEC2_32") (pintype "bidirectional"))
    )
    (net (code "63") (name "Net-(U5-DEC3)") (class "Default")
      (node (ref "C22") (pin "1") (pinfunction "1_1") (pintype "bidirectional"))
      (node (ref "U5") (pin "33") (pinfunction "DEC3_33") (pintype "bidirectional"))
    )
    (net (code "64") (name "Net-(U5-NFC1{slash}P0.09)") (class "Default")
      (node (ref "C29") (pin "1") (pinfunction "1_1") (pintype "bidirectional"))
      (node (ref "J3") (pin "1") (pinfunction "1_1") (pintype "bidirectional"))
      (node (ref "U5") (pin "11") (pinfunction "NFC1/P0.09_11") (pintype "bidirectional"))
    )
    (net (code "65") (name "Net-(U5-NFC2{slash}P0.10)") (class "Default")
      (node (ref "C30") (pin "1") (pinfunction "1_1") (pintype "bidirectional"))
      (node (ref "J3") (pin "2") (pinfunction "2_2") (pintype "bidirectional"))
      (node (ref "J3") (pin "3") (pinfunction "2_3") (pintype "bidirectional"))
      (node (ref "U5") (pin "12") (pinfunction "NFC2/P0.10_12") (pintype "bidirectional"))
    )
    (net (code "66") (name "Net-(U5-P0.00{slash}XL1)") (class "Default")
      (node (ref "C21") (pin "2") (pinfunction "2_2") (pintype "bidirectional"))
      (node (ref "U5") (pin "2") (pinfunction "P0.00/XL1_2") (pintype "bidirectional"))
      (node (ref "Y2") (pin "1") (pinfunction "1_1") (pintype "bidirectional"))
    )
    (net (code "67") (name "Net-(U5-P0.01{slash}XL2)") (class "Default")
      (node (ref "C23") (pin "2") (pinfunction "2_2") (pintype "bidirectional"))
      (node (ref "U5") (pin "3") (pinfunction "P0.01/XL2_3") (pintype "bidirectional"))
      (node (ref "Y2") (pin "2") (pinfunction "2_2") (pintype "bidirectional"))
    )
    (net (code "68") (name "Net-(U5-SC1)") (class "Default")
      (node (ref "C19") (pin "1") (pinfunction "1_1") (pintype "bidirectional"))
      (node (ref "U5") (pin "34") (pinfunction "SC1_34") (pintype "bidirectional"))
      (node (ref "Y1") (pin "1") (pinfunction "1_1") (pintype "bidirectional"))
    )
    (net (code "69") (name "Net-(U5-SC2)") (class "Default")
      (node (ref "C16") (pin "1") (pinfunction "1_1") (pintype "bidirectional"))
      (node (ref "U5") (pin "35") (pinfunction "SC2_35") (pintype "bidirectional"))
      (node (ref "Y1") (pin "3") (pinfunction "3_3") (pintype "bidirectional"))
    )
    (net (code "70") (name "Net-(U6-ASCX)") (class "Default")
      (node (ref "R47") (pin "1") (pinfunction "1_1") (pintype "passive"))
      (node (ref "U6") (pin "3") (pinfunction "ASCX_3") (pintype "bidirectional"))
    )
    (net (code "71") (name "Net-(U6-ASDX)") (class "Default")
      (node (ref "R46") (pin "1") (pinfunction "1_1") (pintype "passive"))
      (node (ref "U6") (pin "2") (pinfunction "ASDX_2") (pintype "bidirectional"))
    )
    (net (code "72") (name "Net-(U6-CSB)") (class "Default")
      (node (ref "R16") (pin "2") (pinfunction "2_2") (pintype "passive"))
      (node (ref "U6") (pin "12") (pinfunction "CSB_12") (pintype "bidirectional"))
    )
    (net (code "73") (name "Net-(U6-INT2)") (class "Default")
      (node (ref "R17") (pin "2") (pinfunction "2_2") (pintype "passive"))
      (node (ref "U6") (pin "9") (pinfunction "INT2_9") (pintype "bidirectional"))
    )
    (net (code "74") (name "Net-(U6-SDO)") (class "Default")
      (node (ref "R13") (pin "1") (pinfunction "1_1") (pintype "passive"))
      (node (ref "U6") (pin "1") (pinfunction "SDO_1") (pintype "bidirectional"))
    )
    (net (code "75") (name "Net-(U6-VDD)") (class "Default")
      (node (ref "C36") (pin "1") (pinfunction "1_1") (pintype "bidirectional"))
      (node (ref "C37") (pin "1") (pinfunction "1_1") (pintype "bidirectional"))
      (node (ref "C38") (pin "1") (pinfunction "1_1") (pintype "bidirectional"))
      (node (ref "R18") (pin "1") (pinfunction "1_1") (pintype "passive"))
      (node (ref "U6") (pin "8") (pinfunction "VDD_8") (pintype "bidirectional"))
    )
    (net (code "76") (name "Net-(U6-VDDIO)") (class "Default")
      (node (ref "C31") (pin "1") (pinfunction "1_1") (pintype "bidirectional"))
      (node (ref "C32") (pin "1") (pinfunction "1_1") (pintype "bidirectional"))
      (node (ref "C35") (pin "1") (pinfunction "1_1") (pintype "bidirectional"))
      (node (ref "R15") (pin "1") (pinfunction "1_1") (pintype "passive"))
      (node (ref "R16") (pin "1") (pinfunction "1_1") (pintype "passive"))
      (node (ref "U6") (pin "5") (pinfunction "VDDIO_5") (pintype "bidirectional"))
    )
    (net (code "77") (name "Net-(U7-1A)") (class "Default")
      (node (ref "D4") (pin "1") (pinfunction "1_1") (pintype "bidirectional"))
      (node (ref "U7") (pin "2") (pinfunction "1A_2") (pintype "bidirectional"))
    )
    (net (code "78") (name "Net-(U7-2A)") (class "Default")
      (node (ref "D4") (pin "2") (pinfunction "2_2") (pintype "bidirectional"))
      (node (ref "U7") (pin "3") (pinfunction "2A_3") (pintype "bidirectional"))
    )
    (net (code "79") (name "Net-(U7-DIR)") (class "Default")
      (node (ref "R20") (pin "1") (pinfunction "1_1") (pintype "passive"))
      (node (ref "R21") (pin "2") (pinfunction "2_2") (pintype "passive"))
      (node (ref "U7") (pin "5") (pinfunction "DIR_5") (pintype "bidirectional"))
    )
    (net (code "80") (name "PWR_EN") (class "Default")
      (node (ref "C33") (pin "1") (pinfunction "1_1") (pintype "bidirectional"))
      (node (ref "R28") (pin "2") (pinfunction "2_2") (pintype "passive"))
      (node (ref "U5") (pin "37") (pinfunction "P0.25_37") (pintype "bidirectional"))
    )
    (net (code "81") (name "RGBLED_MOSI") (class "Default")
      (node (ref "U5") (pin "5") (pinfunction "P0.03/AIN1_5") (pintype "bidirectional"))
      (node (ref "U7") (pin "7") (pinfunction "1B_7") (pintype "bidirectional"))
    )
    (net (code "82") (name "RGBLED_SCK") (class "Default")
      (node (ref "U5") (pin "4") (pinfunction "P0.02/AIN0_4") (pintype "bidirectional"))
      (node (ref "U7") (pin "6") (pinfunction "2B_6") (pintype "bidirectional"))
    )
    (net (code "83") (name "SHT30_RESET") (class "Default")
      (node (ref "R33") (pin "1") (pinfunction "1_1") (pintype "passive"))
      (node (ref "U4") (pin "6") (pinfunction "NRESET_6") (pintype "bidirectional"))
      (node (ref "U5") (pin "18") (pinfunction "P0.15/TRACEDATA2_18") (pintype "bidirectional"))
    )
    (net (code "84") (name "SWDCLK") (class "Default")
      (node (ref "P1") (pin "4") (pinfunction "4_4") (pintype "bidirectional"))
      (node (ref "TP13") (pin "1") (pinfunction "1_1") (pintype "bidirectional"))
      (node (ref "U5") (pin "25") (pinfunction "SWDCLK_25") (pintype "bidirectional"))
    )
    (net (code "85") (name "SWDIO") (class "Default")
      (node (ref "P1") (pin "2") (pinfunction "2_2") (pintype "bidirectional"))
      (node (ref "TP11") (pin "1") (pinfunction "1_1") (pintype "bidirectional"))
      (node (ref "U5") (pin "26") (pinfunction "SWDIO_26") (pintype "bidirectional"))
    )
    (net (code "86") (name "SWO") (class "Default")
      (node (ref "P1") (pin "6") (pinfunction "6_6") (pintype "bidirectional"))
      (node (ref "TP22") (pin "1") (pinfunction "1_1") (pintype "bidirectional"))
      (node (ref "U5") (pin "21") (pinfunction "P0.18/TRACEDATA0/SWO_21") (pintype "bidirectional"))
    )
    (net (code "87") (name "UART_CTS") (class "Default")
      (node (ref "TP19") (pin "1") (pinfunction "1_1") (pintype "bidirectional"))
      (node (ref "U5") (pin "9") (pinfunction "P0.07_9") (pintype "bidirectional"))
    )
    (net (code "88") (name "UART_RTS") (class "Default")
      (node (ref "TP17") (pin "1") (pinfunction "1_1") (pintype "bidirectional"))
      (node (ref "U5") (pin "7") (pinfunction "P0.05/AIN3_7") (pintype "bidirectional"))
    )
    (net (code "89") (name "UART_RXD") (class "Default")
      (node (ref "JP1") (pin "2") (pinfunction "2_2") (pintype "bidirectional"))
      (node (ref "TP20") (pin "1") (pinfunction "1_1") (pintype "bidirectional"))
      (node (ref "U5") (pin "10") (pinfunction "P0.08_10") (pintype "bidirectional"))
    )
    (net (code "90") (name "UART_TXD") (class "Default")
      (node (ref "JP1") (pin "1") (pinfunction "1_1") (pintype "bidirectional"))
      (node (ref "TP18") (pin "1") (pinfunction "1_1") (pintype "bidirectional"))
      (node (ref "U5") (pin "8") (pinfunction "P0.06_8") (pintype "bidirectional"))
    )
    (net (code "91") (name "USB_DETECT") (class "Default")
      (node (ref "R22") (pin "1") (pinfunction "1_1") (pintype "passive"))
      (node (ref "R23") (pin "2") (pinfunction "2_2") (pintype "passive"))
      (node (ref "U5") (pin "43") (pinfunction "P0.31/AIN7_43") (pintype "bidirectional"))
    )
    (net (code "92") (name "UWB_GPIO5") (class "Default")
      (node (ref "U5") (pin "41") (pinfunction "P0.29/AIN5_41") (pintype "bidirectional"))
    )
    (net (code "93") (name "UWB_GPIO6") (class "Default")
      (node (ref "U5") (pin "39") (pinfunction "P0.27_39") (pintype "bidirectional"))
    )
    (net (code "94") (name "UWB_IRQ") (class "Default")
      (node (ref "U5") (pin "29") (pinfunction "P0.24_29") (pintype "bidirectional"))
    )
    (net (code "95") (name "UWB_RSTN") (class "Default")
      (node (ref "U5") (pin "23") (pinfunction "P0.20/TRACECLK_23") (pintype "bidirectional"))
    )
    (net (code "96") (name "UWB_SPICLK") (class "Default")
      (node (ref "U5") (pin "14") (pinfunction "P0.11_14") (pintype "bidirectional"))
    )
    (net (code "97") (name "UWB_SPICSN") (class "Default")
      (node (ref "U5") (pin "20") (pinfunction "P0.17_20") (pintype "bidirectional"))
    )
    (net (code "98") (name "UWB_SPIMISO") (class "Default")
      (node (ref "U5") (pin "16") (pinfunction "P0.13_16") (pintype "bidirectional"))
    )
    (net (code "99") (name "UWB_SPIMOSI") (class "Default")
      (node (ref "U5") (pin "19") (pinfunction "P0.16/TRACEDATA1_19") (pintype "bidirectional"))
    )
    (net (code "100") (name "UWB_WAKEUP") (class "Default")
      (node (ref "U5") (pin "22") (pinfunction "P0.19_22") (pintype "bidirectional"))
    )
    (net (code "101") (name "VBUS") (class "Default")
      (node (ref "C1") (pin "1") (pinfunction "1_1") (pintype "bidirectional"))
      (node (ref "C2") (pin "1") (pinfunction "1_1") (pintype "bidirectional"))
      (node (ref "D10") (pin "1") (pinfunction "1_1") (pintype "bidirectional"))
      (node (ref "J1") (pin "A4") (pinfunction "VBUS1_A4") (pintype "power_in"))
      (node (ref "J1") (pin "A9") (pinfunction "VBUS2_A9") (pintype "power_in"))
      (node (ref "J1") (pin "B4") (pinfunction "VBUS4_B4") (pintype "power_in"))
      (node (ref "J1") (pin "B9") (pinfunction "VBUS3_B9") (pintype "power_in"))
      (node (ref "R22") (pin "2") (pinfunction "2_2") (pintype "passive"))
      (node (ref "R43") (pin "2") (pinfunction "2_2") (pintype "passive"))
      (node (ref "TP1") (pin "1") (pinfunction "1_1") (pintype "bidirectional"))
    )
    (net (code "102") (name "VDD") (class "Default")
      (node (ref "C12") (pin "1") (pinfunction "1_1") (pintype "bidirectional"))
      (node (ref "C13") (pin "1") (pinfunction "1_1") (pintype "bidirectional"))
      (node (ref "C17") (pin "1") (pinfunction "1_1") (pintype "bidirectional"))
      (node (ref "C20") (pin "1") (pinfunction "1_1") (pintype "bidirectional"))
      (node (ref "C27") (pin "1") (pinfunction "1_1") (pintype "bidirectional"))
      (node (ref "C39") (pin "2") (pinfunction "2_2") (pintype "bidirectional"))
      (node (ref "P1") (pin "1") (pinfunction "1_1") (pintype "bidirectional"))
      (node (ref "R11") (pin "2") (pinfunction "2_2") (pintype "passive"))
      (node (ref "R14") (pin "1") (pinfunction "1_1") (pintype "passive"))
      (node (ref "R15") (pin "2") (pinfunction "2_2") (pintype "passive"))
      (node (ref "R18") (pin "2") (pinfunction "2_2") (pintype "passive"))
      (node (ref "R20") (pin "2") (pinfunction "2_2") (pintype "passive"))
      (node (ref "R24") (pin "2") (pinfunction "2_2") (pintype "passive"))
      (node (ref "R33") (pin "2") (pinfunction "2_2") (pintype "passive"))
      (node (ref "R34") (pin "2") (pinfunction "2_2") (pintype "passive"))
      (node (ref "R35") (pin "2") (pinfunction "2_2") (pintype "passive"))
      (node (ref "R4") (pin "2") (pinfunction "2_2") (pintype "passive"))
      (node (ref "R57") (pin "2") (pinfunction "2_2") (pintype "passive"))
      (node (ref "R58") (pin "2") (pinfunction "2_2") (pintype "passive"))
      (node (ref "R59") (pin "2") (pinfunction "2_2") (pintype "passive"))
      (node (ref "R60") (pin "2") (pinfunction "2_2") (pintype "passive"))
      (node (ref "R7") (pin "2") (pinfunction "2_2") (pintype "passive"))
      (node (ref "SP1") (pin "1") (pinfunction "1_1") (pintype "bidirectional"))
      (node (ref "TP10") (pin "1") (pinfunction "1_1") (pintype "bidirectional"))
      (node (ref "U3") (pin "1") (pinfunction "OUT_1") (pintype "bidirectional"))
      (node (ref "U4") (pin "5") (pinfunction "VDD_5") (pintype "bidirectional"))
      (node (ref "U5") (pin "13") (pinfunction "VDD_13") (pintype "bidirectional"))
      (node (ref "U5") (pin "36") (pinfunction "VDD1_36") (pintype "bidirectional"))
      (node (ref "U5") (pin "48") (pinfunction "VDD2_48") (pintype "bidirectional"))
      (node (ref "U7") (pin "8") (pinfunction "VCCB_8") (pintype "bidirectional"))
      (node (ref "VR1") (pin "3") (pinfunction "3_3") (pintype "bidirectional"))
    )
    (net (code "103") (name "VR") (class "Default")
      (node (ref "TP21") (pin "1") (pinfunction "1_1") (pintype "bidirectional"))
      (node (ref "U5") (pin "6") (pinfunction "P0.04/AIN2_6") (pintype "bidirectional"))
      (node (ref "VR1") (pin "2") (pinfunction "2_2") (pintype "bidirectional"))
    )
    (net (code "104") (name "unconnected-(ANT1-Pad2)") (class "Default")
      (node (ref "ANT1") (pin "2") (pinfunction "2_2") (pintype "bidirectional"))
    )
    (net (code "105") (name "unconnected-(D7-Pad5)") (class "Default")
      (node (ref "D7") (pin "5") (pinfunction "5_5") (pintype "bidirectional"))
    )
    (net (code "106") (name "unconnected-(D7-Pad6)") (class "Default")
      (node (ref "D7") (pin "6") (pinfunction "6_6") (pintype "bidirectional"))
    )
    (net (code "107") (name "unconnected-(J1-CC1-PadA5)") (class "Default")
      (node (ref "J1") (pin "A5") (pinfunction "CC1_A5") (pintype "bidirectional"))
    )
    (net (code "108") (name "unconnected-(J1-CC2-PadB5)") (class "Default")
      (node (ref "J1") (pin "B5") (pinfunction "CC2_B5") (pintype "bidirectional"))
    )
    (net (code "109") (name "unconnected-(J1-DN1-PadA7)") (class "Default")
      (node (ref "J1") (pin "A7") (pinfunction "DN1_A7") (pintype "bidirectional"))
    )
    (net (code "110") (name "unconnected-(J1-DN2-PadB7)") (class "Default")
      (node (ref "J1") (pin "B7") (pinfunction "DN2_B7") (pintype "bidirectional"))
    )
    (net (code "111") (name "unconnected-(J1-DP1-PadA6)") (class "Default")
      (node (ref "J1") (pin "A6") (pinfunction "DP1_A6") (pintype "bidirectional"))
    )
    (net (code "112") (name "unconnected-(J1-DP2-PadB6)") (class "Default")
      (node (ref "J1") (pin "B6") (pinfunction "DP2_B6") (pintype "bidirectional"))
    )
    (net (code "113") (name "unconnected-(J1-SBU1-PadA8)") (class "Default")
      (node (ref "J1") (pin "A8") (pinfunction "SBU1_A8") (pintype "bidirectional"))
    )
    (net (code "114") (name "unconnected-(J1-SBU2-PadB8)") (class "Default")
      (node (ref "J1") (pin "B8") (pinfunction "SBU2_B8") (pintype "bidirectional"))
    )
    (net (code "115") (name "unconnected-(J1-SSRXN1-PadB10)") (class "Default")
      (node (ref "J1") (pin "B10") (pinfunction "SSRXN1_B10") (pintype "input"))
    )
    (net (code "116") (name "unconnected-(J1-SSRXN2-PadA10)") (class "Default")
      (node (ref "J1") (pin "A10") (pinfunction "SSRXN2_A10") (pintype "input"))
    )
    (net (code "117") (name "unconnected-(J1-SSRXP1-PadB11)") (class "Default")
      (node (ref "J1") (pin "B11") (pinfunction "SSRXP1_B11") (pintype "input"))
    )
    (net (code "118") (name "unconnected-(J1-SSRXP2-PadA11)") (class "Default")
      (node (ref "J1") (pin "A11") (pinfunction "SSRXP2_A11") (pintype "input"))
    )
    (net (code "119") (name "unconnected-(J1-SSTXN1-PadA3)") (class "Default")
      (node (ref "J1") (pin "A3") (pinfunction "SSTXN1_A3") (pintype "output"))
    )
    (net (code "120") (name "unconnected-(J1-SSTXN2-PadB3)") (class "Default")
      (node (ref "J1") (pin "B3") (pinfunction "SSTXN2_B3") (pintype "output"))
    )
    (net (code "121") (name "unconnected-(J1-SSTXP1-PadA2)") (class "Default")
      (node (ref "J1") (pin "A2") (pinfunction "SSTXP1_A2") (pintype "output"))
    )
    (net (code "122") (name "unconnected-(J1-SSTXP2-PadB2)") (class "Default")
      (node (ref "J1") (pin "B2") (pinfunction "SSTXP2_B2") (pintype "output"))
    )
    (net (code "123") (name "unconnected-(SW3-Pad1)") (class "Default")
      (node (ref "SW3") (pin "1") (pinfunction "1_1") (pintype "bidirectional"))
    )
    (net (code "124") (name "unconnected-(SW3-Pad4)") (class "Default")
      (node (ref "SW3") (pin "4") (pinfunction "4_4") (pintype "bidirectional"))
    )
    (net (code "125") (name "unconnected-(SW3-Pad5)") (class "Default")
      (node (ref "SW3") (pin "5") (pinfunction "5_5") (pintype "bidirectional"))
    )
    (net (code "126") (name "unconnected-(SW3-Pad6)") (class "Default")
      (node (ref "SW3") (pin "6") (pinfunction "6_6") (pintype "bidirectional"))
    )
    (net (code "127") (name "unconnected-(SW4-Pad1)") (class "Default")
      (node (ref "SW4") (pin "1") (pinfunction "1_1") (pintype "bidirectional"))
    )
    (net (code "128") (name "unconnected-(SW4-Pad4)") (class "Default")
      (node (ref "SW4") (pin "4") (pinfunction "4_4") (pintype "bidirectional"))
    )
    (net (code "129") (name "unconnected-(U1-NC1-Pad2)") (class "Default")
      (node (ref "U1") (pin "2") (pinfunction "NC1_2") (pintype "no_connect"))
    )
    (net (code "130") (name "unconnected-(U1-NC2-Pad7)") (class "Default")
      (node (ref "U1") (pin "7") (pinfunction "NC2_7") (pintype "no_connect"))
    )
    (net (code "131") (name "unconnected-(U4-ALERT-Pad3)") (class "Default")
      (node (ref "U4") (pin "3") (pinfunction "ALERT_3") (pintype "bidirectional"))
    )
    (net (code "132") (name "unconnected-(U5-NC-Pad44)") (class "Default")
      (node (ref "U5") (pin "44") (pinfunction "NC_44") (pintype "no_connect"))
    )
    (net (code "133") (name "unconnected-(U6-OSCB-Pad10)") (class "Default")
      (node (ref "U6") (pin "10") (pinfunction "OSCB_10") (pintype "bidirectional"))
    )
    (net (code "134") (name "unconnected-(U6-OSDO-Pad11)") (class "Default")
      (node (ref "U6") (pin "11") (pinfunction "OSDO_11") (pintype "bidirectional"))
    )
  )
)
